# axiom_beta_sensor_cmv12000_tht_v0_16_r1_.net
KiCad netlist of a schematic drawn in EAGLE
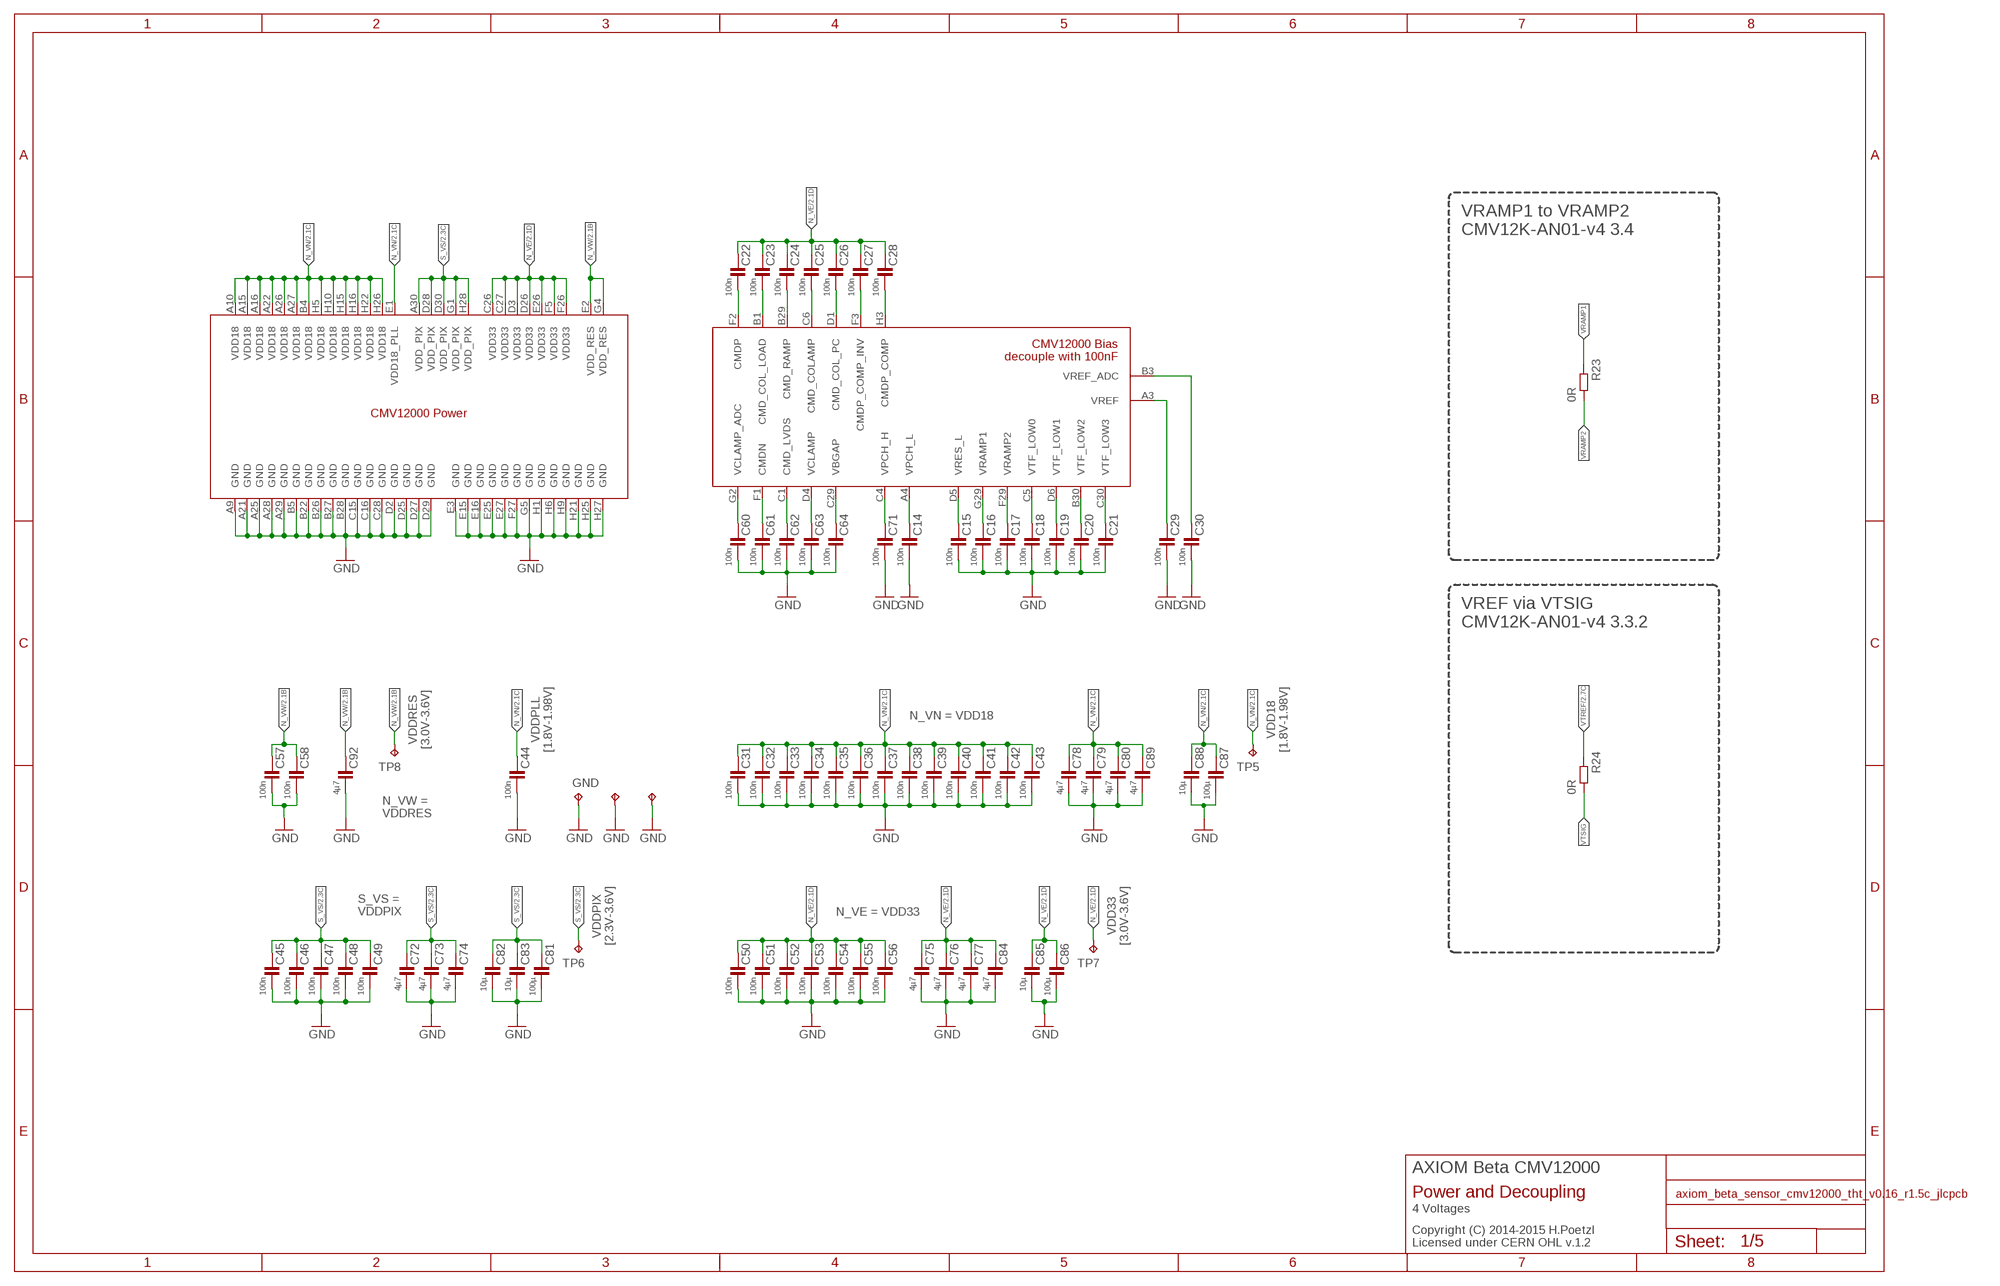
[diagram p0: schematic, sheet 1]
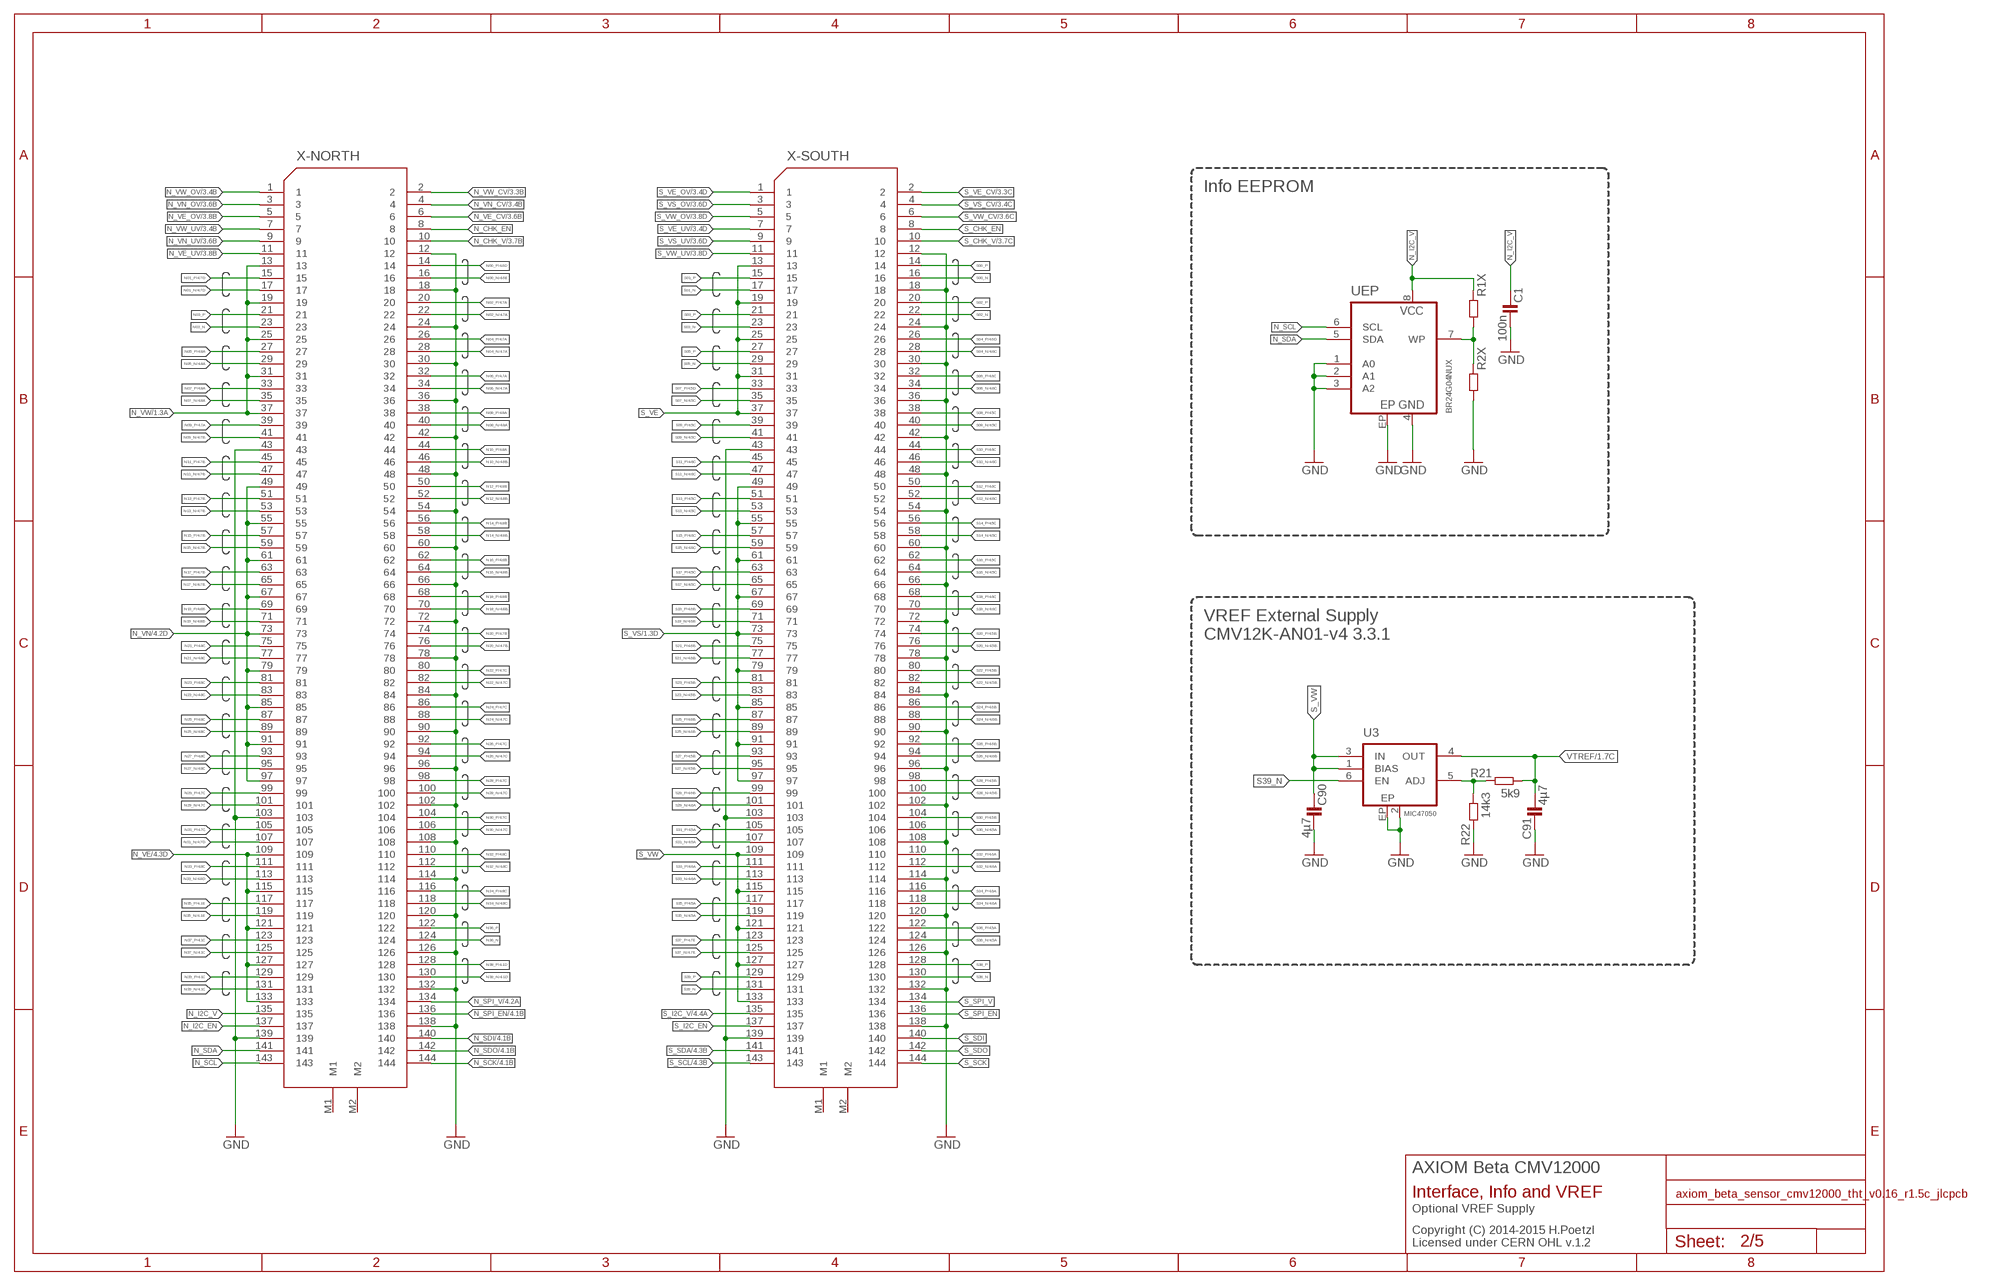
[diagram p1: schematic, sheet 2]
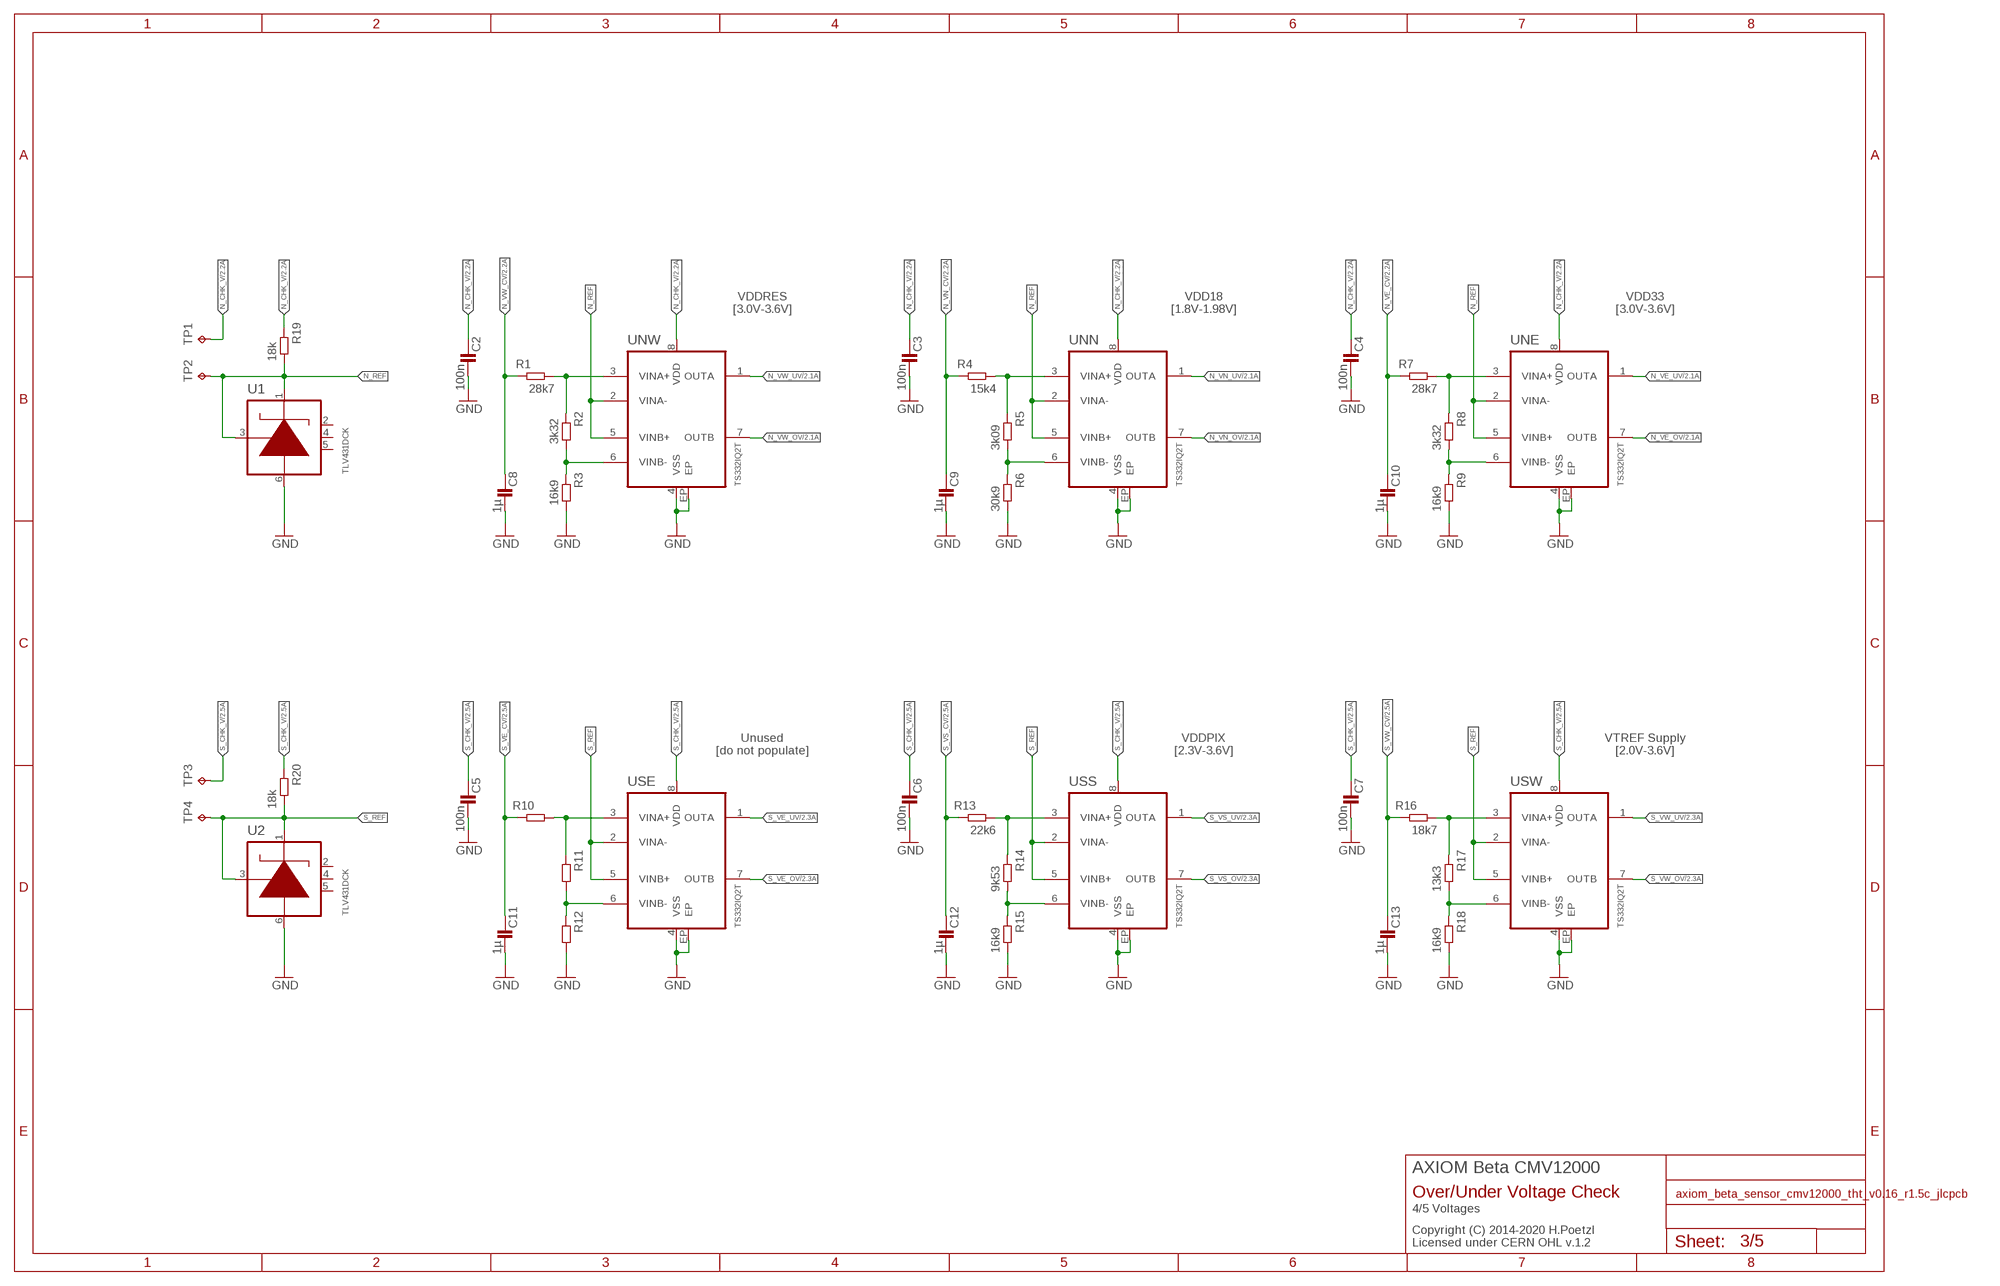
[diagram p2: schematic, sheet 3]
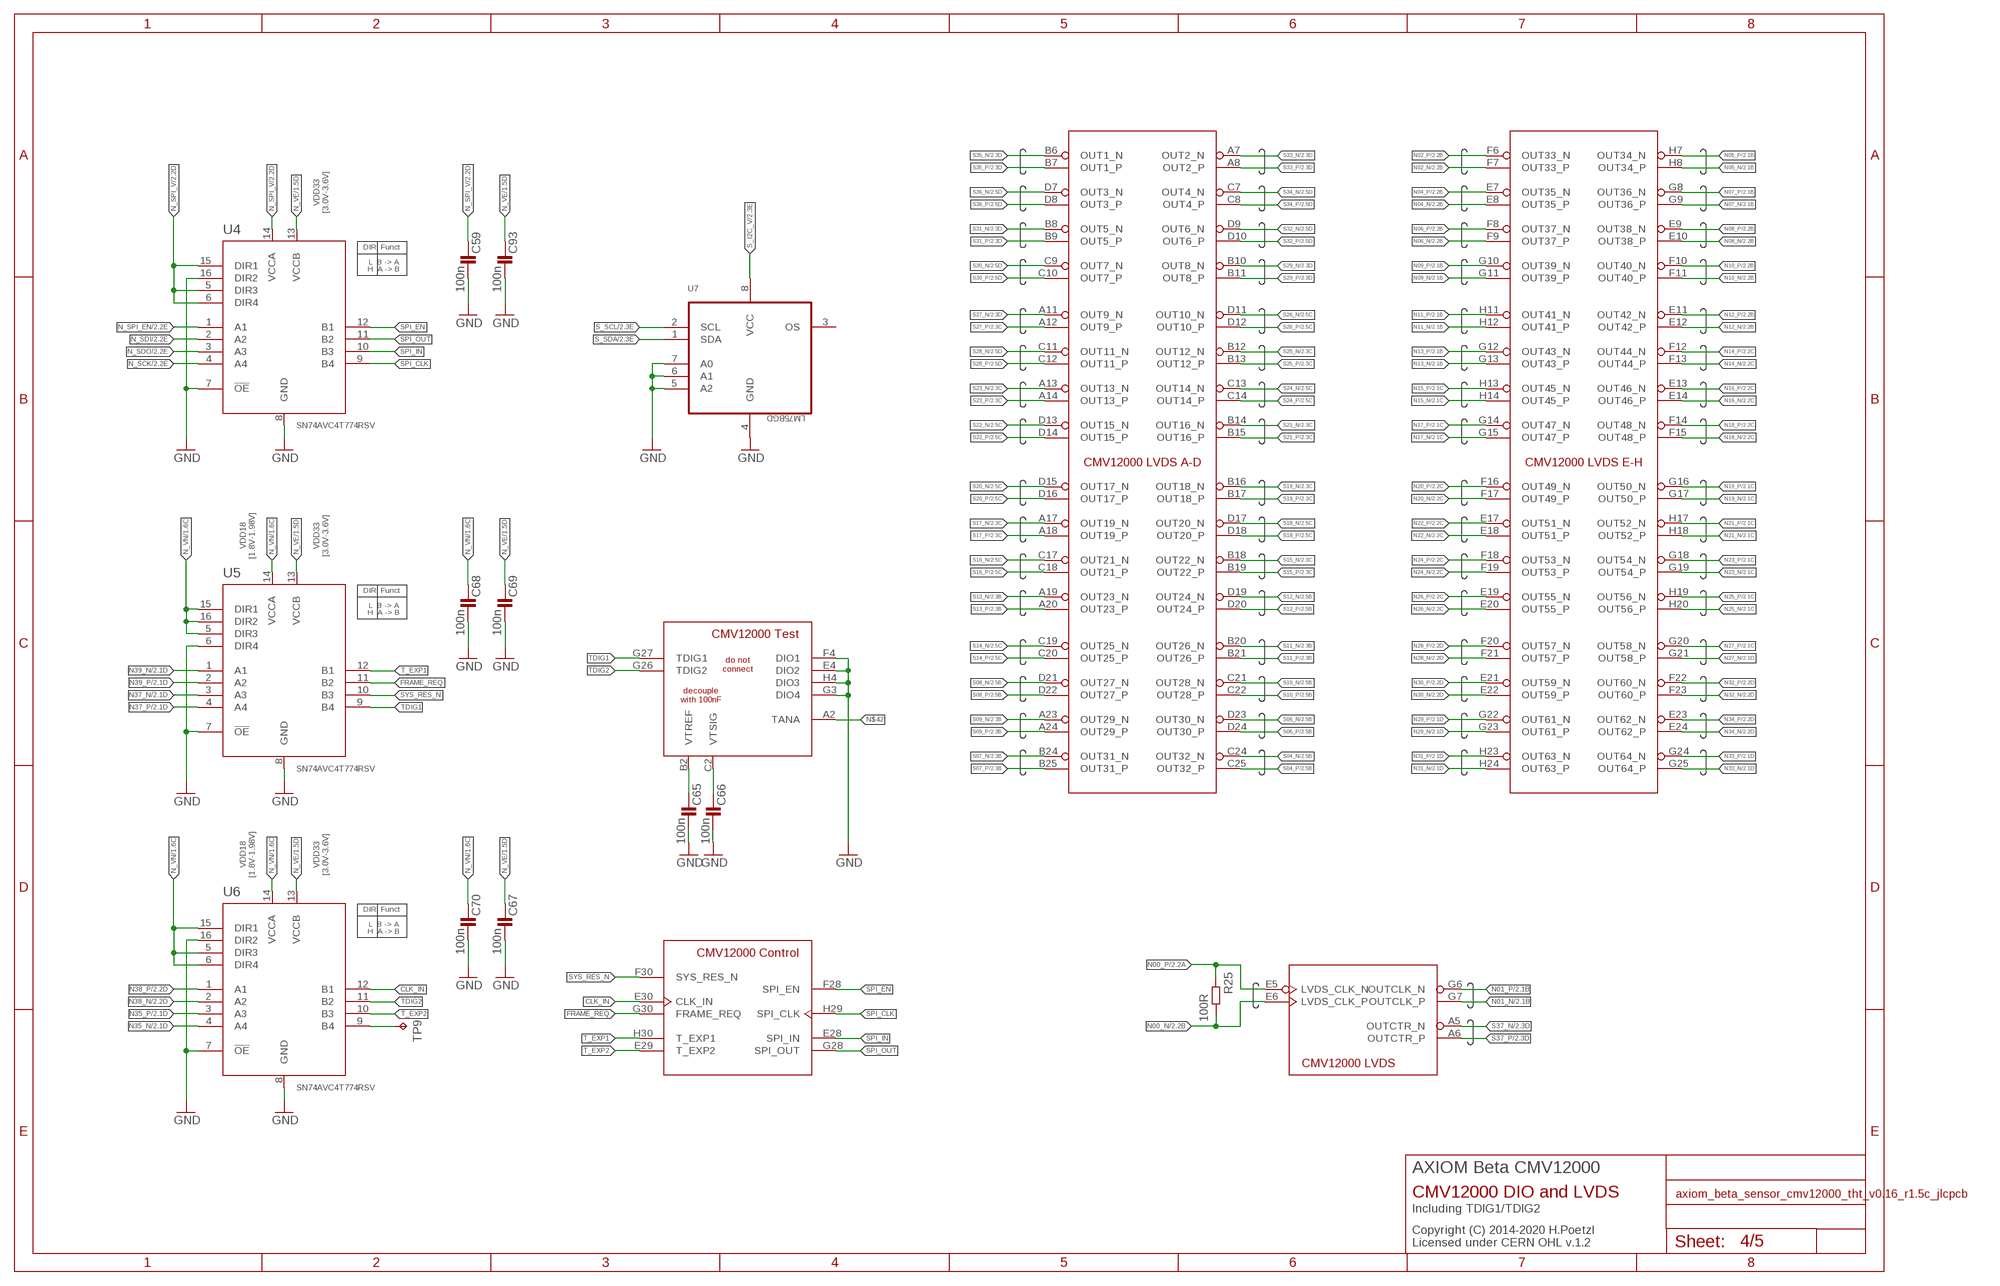
[diagram p3: schematic, sheet 4]
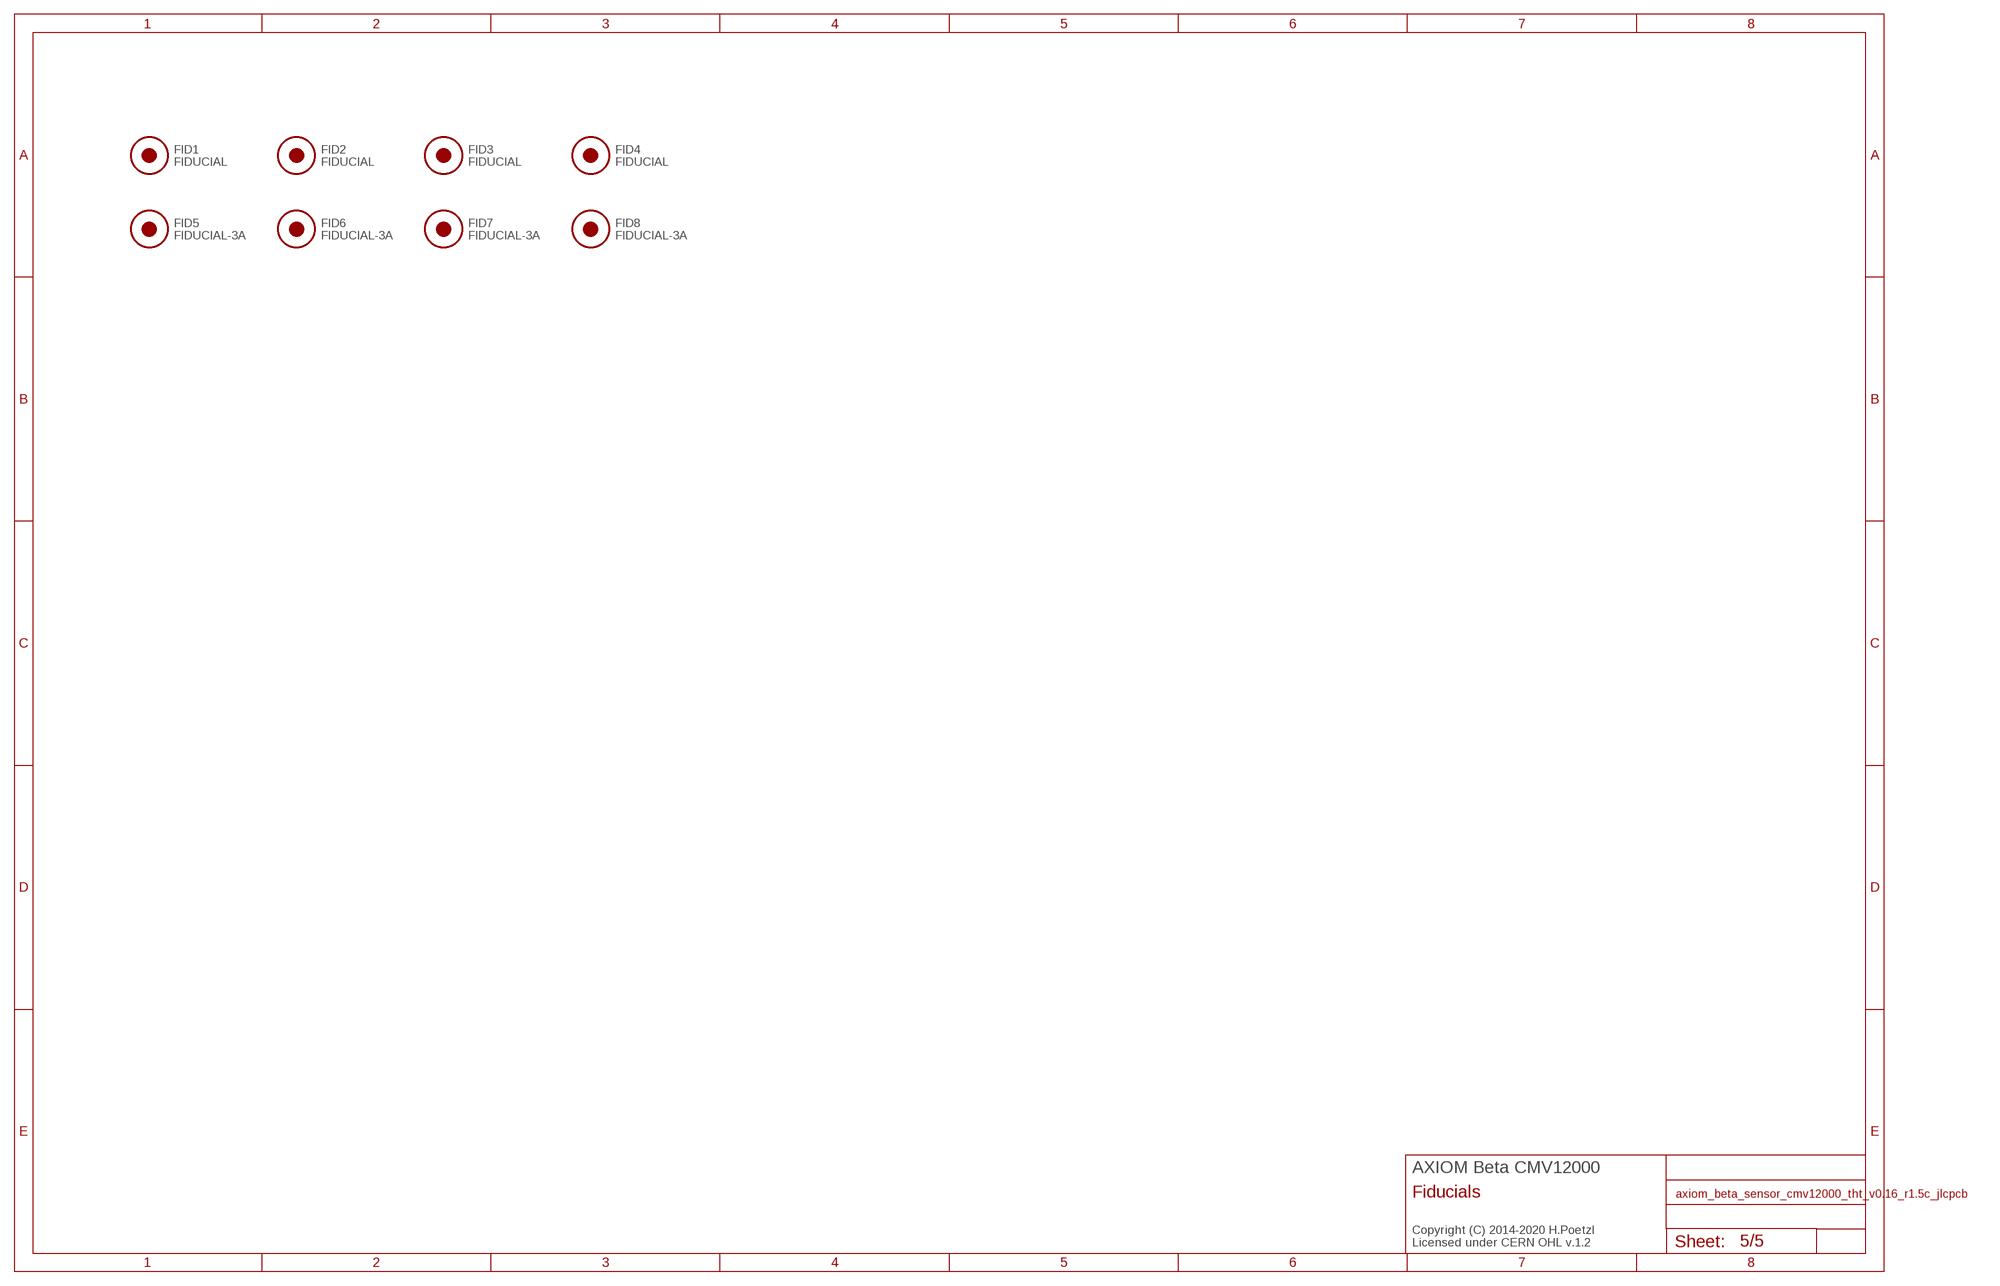
[diagram p4: schematic, sheet 5]

(export (version "E")
  (design (tool "Eeschema 10.0.6"))
  (components
    (comp (ref "C2")
      (value "100n")
      (footprint "eagle-import:0402-C")
      (libsource (lib "eagle-import") (part "C0402-C"))
    )
    (comp (ref "C3")
      (value "100n")
      (footprint "eagle-import:0402-C")
      (libsource (lib "eagle-import") (part "C0402-C"))
    )
    (comp (ref "C4")
      (value "100n")
      (footprint "eagle-import:0402-C")
      (libsource (lib "eagle-import") (part "C0402-C"))
    )
    (comp (ref "C5")
      (value "100n")
      (footprint "eagle-import:0402-C")
      (libsource (lib "eagle-import") (part "C0402-C"))
    )
    (comp (ref "C6")
      (value "100n")
      (footprint "eagle-import:0402-C")
      (libsource (lib "eagle-import") (part "C0402-C"))
    )
    (comp (ref "C7")
      (value "100n")
      (footprint "eagle-import:0402-C")
      (libsource (lib "eagle-import") (part "C0402-C"))
    )
    (comp (ref "C8")
      (value "1µ")
      (footprint "eagle-import:0402-C")
      (libsource (lib "eagle-import") (part "C0402-C"))
    )
    (comp (ref "C9")
      (value "1µ")
      (footprint "eagle-import:0402-C")
      (libsource (lib "eagle-import") (part "C0402-C"))
    )
    (comp (ref "C10")
      (value "1µ")
      (footprint "eagle-import:0402-C")
      (libsource (lib "eagle-import") (part "C0402-C"))
    )
    (comp (ref "C11")
      (value "1µ")
      (footprint "eagle-import:0402-C")
      (libsource (lib "eagle-import") (part "C0402-C"))
    )
    (comp (ref "C12")
      (value "1µ")
      (footprint "eagle-import:0402-C")
      (libsource (lib "eagle-import") (part "C0402-C"))
    )
    (comp (ref "C13")
      (value "1µ")
      (footprint "eagle-import:0402-C")
      (libsource (lib "eagle-import") (part "C0402-C"))
    )
    (comp (ref "R1")
      (value "28k7")
      (footprint "eagle-import:0402-C")
      (libsource (lib "eagle-import") (part "R0402-C"))
    )
    (comp (ref "R2")
      (value "3k32")
      (footprint "eagle-import:0402-C")
      (libsource (lib "eagle-import") (part "R0402-C"))
    )
    (comp (ref "R3")
      (value "16k9")
      (footprint "eagle-import:0402-C")
      (libsource (lib "eagle-import") (part "R0402-C"))
    )
    (comp (ref "R4")
      (value "15k4")
      (footprint "eagle-import:0402-C")
      (libsource (lib "eagle-import") (part "R0402-C"))
    )
    (comp (ref "R5")
      (value "3k09")
      (footprint "eagle-import:0402-C")
      (libsource (lib "eagle-import") (part "R0402-C"))
    )
    (comp (ref "R6")
      (value "30k9")
      (footprint "eagle-import:0402-C")
      (libsource (lib "eagle-import") (part "R0402-C"))
    )
    (comp (ref "R7")
      (value "28k7")
      (footprint "eagle-import:0402-C")
      (libsource (lib "eagle-import") (part "R0402-C"))
    )
    (comp (ref "R8")
      (value "3k32")
      (footprint "eagle-import:0402-C")
      (libsource (lib "eagle-import") (part "R0402-C"))
    )
    (comp (ref "R9")
      (value "16k9")
      (footprint "eagle-import:0402-C")
      (libsource (lib "eagle-import") (part "R0402-C"))
    )
    (comp (ref "R10")
      (value "R0402-C")
      (footprint "eagle-import:0402-C")
      (libsource (lib "eagle-import") (part "R0402-C"))
    )
    (comp (ref "R11")
      (value "R0402-C")
      (footprint "eagle-import:0402-C")
      (libsource (lib "eagle-import") (part "R0402-C"))
    )
    (comp (ref "R12")
      (value "R0402-C")
      (footprint "eagle-import:0402-C")
      (libsource (lib "eagle-import") (part "R0402-C"))
    )
    (comp (ref "R13")
      (value "22k6")
      (footprint "eagle-import:0402-C")
      (libsource (lib "eagle-import") (part "R0402-C"))
    )
    (comp (ref "R14")
      (value "9k53")
      (footprint "eagle-import:0402-C")
      (libsource (lib "eagle-import") (part "R0402-C"))
    )
    (comp (ref "R15")
      (value "16k9")
      (footprint "eagle-import:0402-C")
      (libsource (lib "eagle-import") (part "R0402-C"))
    )
    (comp (ref "R16")
      (value "18k7")
      (footprint "eagle-import:0402-C")
      (libsource (lib "eagle-import") (part "R0402-C"))
    )
    (comp (ref "R17")
      (value "13k3")
      (footprint "eagle-import:0402-C")
      (libsource (lib "eagle-import") (part "R0402-C"))
    )
    (comp (ref "R18")
      (value "16k9")
      (footprint "eagle-import:0402-C")
      (libsource (lib "eagle-import") (part "R0402-C"))
    )
    (comp (ref "R19")
      (value "18k")
      (footprint "eagle-import:0402-C")
      (libsource (lib "eagle-import") (part "R0402-C"))
    )
    (comp (ref "R20")
      (value "18k")
      (footprint "eagle-import:0402-C")
      (libsource (lib "eagle-import") (part "R0402-C"))
    )
    (comp (ref "TP1")
      (value "TPTP10R")
      (footprint "eagle-import:TP10R")
      (libsource (lib "eagle-import") (part "TPTP10R"))
    )
    (comp (ref "TP2")
      (value "TPTP10R")
      (footprint "eagle-import:TP10R")
      (libsource (lib "eagle-import") (part "TPTP10R"))
    )
    (comp (ref "TP3")
      (value "TPTP10R")
      (footprint "eagle-import:TP10R")
      (libsource (lib "eagle-import") (part "TPTP10R"))
    )
    (comp (ref "TP4")
      (value "TPTP10R")
      (footprint "eagle-import:TP10R")
      (libsource (lib "eagle-import") (part "TPTP10R"))
    )
    (comp (ref "U1")
      (value "TLV431DCK")
      (footprint "eagle-import:SOT65P210X110-6N")
      (libsource (lib "eagle-import") (part "TLV431DCK"))
    )
    (comp (ref "U2")
      (value "TLV431DCK")
      (footprint "eagle-import:SOT65P210X110-6N")
      (libsource (lib "eagle-import") (part "TLV431DCK"))
    )
    (comp (ref "UNE")
      (value "TS332IQ2T")
      (footprint "eagle-import:DFN200X200X100-9N")
      (libsource (lib "eagle-import") (part "TS332IQ2T"))
    )
    (comp (ref "UNN")
      (value "TS332IQ2T")
      (footprint "eagle-import:DFN200X200X100-9N")
      (libsource (lib "eagle-import") (part "TS332IQ2T"))
    )
    (comp (ref "UNW")
      (value "TS332IQ2T")
      (footprint "eagle-import:DFN200X200X100-9N")
      (libsource (lib "eagle-import") (part "TS332IQ2T"))
    )
    (comp (ref "USE")
      (value "TS332IQ2T")
      (footprint "eagle-import:DFN200X200X100-9N")
      (libsource (lib "eagle-import") (part "TS332IQ2T"))
    )
    (comp (ref "USS")
      (value "TS332IQ2T")
      (footprint "eagle-import:DFN200X200X100-9N")
      (libsource (lib "eagle-import") (part "TS332IQ2T"))
    )
    (comp (ref "USW")
      (value "TS332IQ2T")
      (footprint "eagle-import:DFN200X200X100-9N")
      (libsource (lib "eagle-import") (part "TS332IQ2T"))
    )
    (comp (ref "C14")
      (value "100n")
      (footprint "eagle-import:0402-C")
      (libsource (lib "eagle-import") (part "C0402-C"))
    )
    (comp (ref "C15")
      (value "100n")
      (footprint "eagle-import:0402-C")
      (libsource (lib "eagle-import") (part "C0402-C"))
    )
    (comp (ref "C16")
      (value "100n")
      (footprint "eagle-import:0402-C")
      (libsource (lib "eagle-import") (part "C0402-C"))
    )
    (comp (ref "C17")
      (value "100n")
      (footprint "eagle-import:0402-C")
      (libsource (lib "eagle-import") (part "C0402-C"))
    )
    (comp (ref "C18")
      (value "100n")
      (footprint "eagle-import:0402-C")
      (libsource (lib "eagle-import") (part "C0402-C"))
    )
    (comp (ref "C19")
      (value "100n")
      (footprint "eagle-import:0402-C")
      (libsource (lib "eagle-import") (part "C0402-C"))
    )
    (comp (ref "C20")
      (value "100n")
      (footprint "eagle-import:0402-C")
      (libsource (lib "eagle-import") (part "C0402-C"))
    )
    (comp (ref "C21")
      (value "100n")
      (footprint "eagle-import:0402-C")
      (libsource (lib "eagle-import") (part "C0402-C"))
    )
    (comp (ref "C22")
      (value "100n")
      (footprint "eagle-import:0402-C")
      (libsource (lib "eagle-import") (part "C0402-C"))
    )
    (comp (ref "C23")
      (value "100n")
      (footprint "eagle-import:0402-C")
      (libsource (lib "eagle-import") (part "C0402-C"))
    )
    (comp (ref "C24")
      (value "100n")
      (footprint "eagle-import:0402-C")
      (libsource (lib "eagle-import") (part "C0402-C"))
    )
    (comp (ref "C25")
      (value "100n")
      (footprint "eagle-import:0402-C")
      (libsource (lib "eagle-import") (part "C0402-C"))
    )
    (comp (ref "C26")
      (value "100n")
      (footprint "eagle-import:0402-C")
      (libsource (lib "eagle-import") (part "C0402-C"))
    )
    (comp (ref "C27")
      (value "100n")
      (footprint "eagle-import:0402-C")
      (libsource (lib "eagle-import") (part "C0402-C"))
    )
    (comp (ref "C28")
      (value "100n")
      (footprint "eagle-import:0402-C")
      (libsource (lib "eagle-import") (part "C0402-C"))
    )
    (comp (ref "C29")
      (value "100n")
      (footprint "eagle-import:0402-C")
      (libsource (lib "eagle-import") (part "C0402-C"))
    )
    (comp (ref "C30")
      (value "100n")
      (footprint "eagle-import:0402-C")
      (libsource (lib "eagle-import") (part "C0402-C"))
    )
    (comp (ref "C31")
      (value "100n")
      (footprint "eagle-import:0402-C")
      (libsource (lib "eagle-import") (part "C0402-C"))
    )
    (comp (ref "C32")
      (value "100n")
      (footprint "eagle-import:0402-C")
      (libsource (lib "eagle-import") (part "C0402-C"))
    )
    (comp (ref "C33")
      (value "100n")
      (footprint "eagle-import:0402-C")
      (libsource (lib "eagle-import") (part "C0402-C"))
    )
    (comp (ref "C34")
      (value "100n")
      (footprint "eagle-import:0402-C")
      (libsource (lib "eagle-import") (part "C0402-C"))
    )
    (comp (ref "C35")
      (value "100n")
      (footprint "eagle-import:0402-C")
      (libsource (lib "eagle-import") (part "C0402-C"))
    )
    (comp (ref "C36")
      (value "100n")
      (footprint "eagle-import:0402-C")
      (libsource (lib "eagle-import") (part "C0402-C"))
    )
    (comp (ref "C37")
      (value "100n")
      (footprint "eagle-import:0402-C")
      (libsource (lib "eagle-import") (part "C0402-C"))
    )
    (comp (ref "C38")
      (value "100n")
      (footprint "eagle-import:0402-C")
      (libsource (lib "eagle-import") (part "C0402-C"))
    )
    (comp (ref "C39")
      (value "100n")
      (footprint "eagle-import:0402-C")
      (libsource (lib "eagle-import") (part "C0402-C"))
    )
    (comp (ref "C40")
      (value "100n")
      (footprint "eagle-import:0402-C")
      (libsource (lib "eagle-import") (part "C0402-C"))
    )
    (comp (ref "C41")
      (value "100n")
      (footprint "eagle-import:0402-C")
      (libsource (lib "eagle-import") (part "C0402-C"))
    )
    (comp (ref "C42")
      (value "100n")
      (footprint "eagle-import:0402-C")
      (libsource (lib "eagle-import") (part "C0402-C"))
    )
    (comp (ref "C43")
      (value "100n")
      (footprint "eagle-import:0402-C")
      (libsource (lib "eagle-import") (part "C0402-C"))
    )
    (comp (ref "C44")
      (value "100n")
      (footprint "eagle-import:0402-C")
      (libsource (lib "eagle-import") (part "C0402-C"))
    )
    (comp (ref "C45")
      (value "100n")
      (footprint "eagle-import:0402-C")
      (libsource (lib "eagle-import") (part "C0402-C"))
    )
    (comp (ref "C46")
      (value "100n")
      (footprint "eagle-import:0402-C")
      (libsource (lib "eagle-import") (part "C0402-C"))
    )
    (comp (ref "C47")
      (value "100n")
      (footprint "eagle-import:0402-C")
      (libsource (lib "eagle-import") (part "C0402-C"))
    )
    (comp (ref "C48")
      (value "100n")
      (footprint "eagle-import:0402-C")
      (libsource (lib "eagle-import") (part "C0402-C"))
    )
    (comp (ref "C49")
      (value "100n")
      (footprint "eagle-import:0402-C")
      (libsource (lib "eagle-import") (part "C0402-C"))
    )
    (comp (ref "C50")
      (value "100n")
      (footprint "eagle-import:0402-C")
      (libsource (lib "eagle-import") (part "C0402-C"))
    )
    (comp (ref "C51")
      (value "100n")
      (footprint "eagle-import:0402-C")
      (libsource (lib "eagle-import") (part "C0402-C"))
    )
    (comp (ref "C52")
      (value "100n")
      (footprint "eagle-import:0402-C")
      (libsource (lib "eagle-import") (part "C0402-C"))
    )
    (comp (ref "C53")
      (value "100n")
      (footprint "eagle-import:0402-C")
      (libsource (lib "eagle-import") (part "C0402-C"))
    )
    (comp (ref "C54")
      (value "100n")
      (footprint "eagle-import:0402-C")
      (libsource (lib "eagle-import") (part "C0402-C"))
    )
    (comp (ref "C55")
      (value "100n")
      (footprint "eagle-import:0402-C")
      (libsource (lib "eagle-import") (part "C0402-C"))
    )
    (comp (ref "C56")
      (value "100n")
      (footprint "eagle-import:0402-C")
      (libsource (lib "eagle-import") (part "C0402-C"))
    )
    (comp (ref "C57")
      (value "100n")
      (footprint "eagle-import:0402-C")
      (libsource (lib "eagle-import") (part "C0402-C"))
    )
    (comp (ref "C58")
      (value "100n")
      (footprint "eagle-import:0402-C")
      (libsource (lib "eagle-import") (part "C0402-C"))
    )
    (comp (ref "C60")
      (value "100n")
      (footprint "eagle-import:0402-C")
      (libsource (lib "eagle-import") (part "C0402-C"))
    )
    (comp (ref "C61")
      (value "100n")
      (footprint "eagle-import:0402-C")
      (libsource (lib "eagle-import") (part "C0402-C"))
    )
    (comp (ref "C62")
      (value "100n")
      (footprint "eagle-import:0402-C")
      (libsource (lib "eagle-import") (part "C0402-C"))
    )
    (comp (ref "C63")
      (value "100n")
      (footprint "eagle-import:0402-C")
      (libsource (lib "eagle-import") (part "C0402-C"))
    )
    (comp (ref "C64")
      (value "100n")
      (footprint "eagle-import:0402-C")
      (libsource (lib "eagle-import") (part "C0402-C"))
    )
    (comp (ref "C71")
      (value "100n")
      (footprint "eagle-import:0402-C")
      (libsource (lib "eagle-import") (part "C0402-C"))
    )
    (comp (ref "C72")
      (value "4µ7")
      (footprint "eagle-import:0402-B")
      (libsource (lib "eagle-import") (part "C0402-B"))
    )
    (comp (ref "C73")
      (value "4µ7")
      (footprint "eagle-import:0402-C")
      (libsource (lib "eagle-import") (part "C0402-C"))
    )
    (comp (ref "C74")
      (value "4µ7")
      (footprint "eagle-import:0402-C")
      (libsource (lib "eagle-import") (part "C0402-C"))
    )
    (comp (ref "C75")
      (value "4µ7")
      (footprint "eagle-import:0402-C")
      (libsource (lib "eagle-import") (part "C0402-C"))
    )
    (comp (ref "C76")
      (value "4µ7")
      (footprint "eagle-import:0402-C")
      (libsource (lib "eagle-import") (part "C0402-C"))
    )
    (comp (ref "C77")
      (value "4µ7")
      (footprint "eagle-import:0402-B")
      (libsource (lib "eagle-import") (part "C0402-B"))
    )
    (comp (ref "C78")
      (value "4µ7")
      (footprint "eagle-import:0402-B")
      (libsource (lib "eagle-import") (part "C0402-B"))
    )
    (comp (ref "C79")
      (value "4µ7")
      (footprint "eagle-import:0402-C")
      (libsource (lib "eagle-import") (part "C0402-C"))
    )
    (comp (ref "C80")
      (value "4µ7")
      (footprint "eagle-import:0402-C")
      (libsource (lib "eagle-import") (part "C0402-C"))
    )
    (comp (ref "C81")
      (value "100µ")
      (footprint "eagle-import:1206-B")
      (libsource (lib "eagle-import") (part "C1206-B"))
    )
    (comp (ref "C82")
      (value "10µ")
      (footprint "eagle-import:0603-C")
      (libsource (lib "eagle-import") (part "C0603-C"))
    )
    (comp (ref "C83")
      (value "10µ")
      (footprint "eagle-import:0603-C")
      (libsource (lib "eagle-import") (part "C0603-C"))
    )
    (comp (ref "C84")
      (value "4µ7")
      (footprint "eagle-import:0402-C")
      (libsource (lib "eagle-import") (part "C0402-C"))
    )
    (comp (ref "C85")
      (value "10µ")
      (footprint "eagle-import:0603-C")
      (libsource (lib "eagle-import") (part "C0603-C"))
    )
    (comp (ref "C86")
      (value "100µ")
      (footprint "eagle-import:1206-B")
      (libsource (lib "eagle-import") (part "C1206-B"))
    )
    (comp (ref "C87")
      (value "100µ")
      (footprint "eagle-import:1206-B")
      (libsource (lib "eagle-import") (part "C1206-B"))
    )
    (comp (ref "C88")
      (value "10µ")
      (footprint "eagle-import:0603-C")
      (libsource (lib "eagle-import") (part "C0603-C"))
    )
    (comp (ref "C89")
      (value "4µ7")
      (footprint "eagle-import:0402-C")
      (libsource (lib "eagle-import") (part "C0402-C"))
    )
    (comp (ref "C92")
      (value "4µ7")
      (footprint "eagle-import:0402-C")
      (libsource (lib "eagle-import") (part "C0402-C"))
    )
    (comp (ref "GND")
      (value "TPTP10R")
      (footprint "eagle-import:TP10R")
      (libsource (lib "eagle-import") (part "TPTP10R"))
    )
    (comp (ref "GND75")
      (value "TPTP10R")
      (footprint "eagle-import:TP10R")
      (libsource (lib "eagle-import") (part "TPTP10R"))
    )
    (comp (ref "GND77")
      (value "TPTP10R")
      (footprint "eagle-import:TP10R")
      (libsource (lib "eagle-import") (part "TPTP10R"))
    )
    (comp (ref "R23")
      (value "0R")
      (footprint "eagle-import:0402-C")
      (libsource (lib "eagle-import") (part "R0402-C"))
    )
    (comp (ref "R24")
      (value "0R")
      (footprint "eagle-import:0402-C")
      (libsource (lib "eagle-import") (part "R0402-C"))
    )
    (comp (ref "SENSOR")
      (value "CMV12000JLCPCB")
      (footprint "eagle-import:10-30-07-237-400T4-JLCPCB")
      (libsource (lib "eagle-import") (part "CMV12000JLCPCB"))
    )
    (comp (ref "TP5")
      (value "TPTP10R")
      (footprint "eagle-import:TP10R")
      (libsource (lib "eagle-import") (part "TPTP10R"))
    )
    (comp (ref "TP6")
      (value "TPTP10R")
      (footprint "eagle-import:TP10R")
      (libsource (lib "eagle-import") (part "TPTP10R"))
    )
    (comp (ref "TP7")
      (value "TPTP10R")
      (footprint "eagle-import:TP10R")
      (libsource (lib "eagle-import") (part "TPTP10R"))
    )
    (comp (ref "TP8")
      (value "TPTP10R")
      (footprint "eagle-import:TP10R")
      (libsource (lib "eagle-import") (part "TPTP10R"))
    )
    (comp (ref "FID1")
      (value "FIDUCIAL")
      (footprint "eagle-import:FID_ARROW")
      (libsource (lib "eagle-import") (part "FIDUCIAL"))
    )
    (comp (ref "FID2")
      (value "FIDUCIAL")
      (footprint "eagle-import:FID_ARROW")
      (libsource (lib "eagle-import") (part "FIDUCIAL"))
    )
    (comp (ref "FID3")
      (value "FIDUCIAL")
      (footprint "eagle-import:FID_ARROW")
      (libsource (lib "eagle-import") (part "FIDUCIAL"))
    )
    (comp (ref "FID4")
      (value "FIDUCIAL")
      (footprint "eagle-import:FID_ARROW")
      (libsource (lib "eagle-import") (part "FIDUCIAL"))
    )
    (comp (ref "FID5")
      (value "FIDUCIAL-3A")
      (footprint "eagle-import:FID_3ARROW")
      (libsource (lib "eagle-import") (part "FIDUCIAL-3A"))
    )
    (comp (ref "FID6")
      (value "FIDUCIAL-3A")
      (footprint "eagle-import:FID_3ARROW")
      (libsource (lib "eagle-import") (part "FIDUCIAL-3A"))
    )
    (comp (ref "FID7")
      (value "FIDUCIAL-3A")
      (footprint "eagle-import:FID_3ARROW")
      (libsource (lib "eagle-import") (part "FIDUCIAL-3A"))
    )
    (comp (ref "FID8")
      (value "FIDUCIAL-3A")
      (footprint "eagle-import:FID_3ARROW")
      (libsource (lib "eagle-import") (part "FIDUCIAL-3A"))
    )
    (comp (ref "C1")
      (value "100n")
      (footprint "eagle-import:0402-C")
      (libsource (lib "eagle-import") (part "C0402-C"))
    )
    (comp (ref "C90")
      (value "4µ7")
      (footprint "eagle-import:0402-C")
      (libsource (lib "eagle-import") (part "C0402-C"))
    )
    (comp (ref "C91")
      (value "4µ7")
      (footprint "eagle-import:0402-C")
      (libsource (lib "eagle-import") (part "C0402-C"))
    )
    (comp (ref "R1X")
      (value "R0402-C")
      (footprint "eagle-import:0402-C")
      (libsource (lib "eagle-import") (part "R0402-C"))
    )
    (comp (ref "R2X")
      (value "R0402-C")
      (footprint "eagle-import:0402-C")
      (libsource (lib "eagle-import") (part "R0402-C"))
    )
    (comp (ref "R21")
      (value "5k9")
      (footprint "eagle-import:0402-C")
      (libsource (lib "eagle-import") (part "R0402-C"))
    )
    (comp (ref "R22")
      (value "14k3")
      (footprint "eagle-import:0402-C")
      (libsource (lib "eagle-import") (part "R0402-C"))
    )
    (comp (ref "U3")
      (value "MIC47050")
      (footprint "eagle-import:MLF-6")
      (libsource (lib "eagle-import") (part "MIC47050-ADJ"))
    )
    (comp (ref "UEP")
      (value "BR24G04NUX")
      (footprint "eagle-import:DFN200X300X100-9N")
      (libsource (lib "eagle-import") (part "BR24G04NUX"))
    )
    (comp (ref "X-NORTH")
      (value "FX10-144P")
      (footprint "eagle-import:FX10A-144P")
      (libsource (lib "eagle-import") (part "FX10-144P"))
    )
    (comp (ref "X-SOUTH")
      (value "FX10-144P")
      (footprint "eagle-import:FX10A-144P")
      (libsource (lib "eagle-import") (part "FX10-144P"))
    )
    (comp (ref "C59")
      (value "100n")
      (footprint "eagle-import:0402-C")
      (libsource (lib "eagle-import") (part "C0402-C"))
    )
    (comp (ref "C65")
      (value "100n")
      (footprint "eagle-import:0402-C")
      (libsource (lib "eagle-import") (part "C0402-C"))
    )
    (comp (ref "C66")
      (value "100n")
      (footprint "eagle-import:0402-C")
      (libsource (lib "eagle-import") (part "C0402-C"))
    )
    (comp (ref "C67")
      (value "100n")
      (footprint "eagle-import:0402-C")
      (libsource (lib "eagle-import") (part "C0402-C"))
    )
    (comp (ref "C68")
      (value "100n")
      (footprint "eagle-import:0402-C")
      (libsource (lib "eagle-import") (part "C0402-C"))
    )
    (comp (ref "C69")
      (value "100n")
      (footprint "eagle-import:0402-C")
      (libsource (lib "eagle-import") (part "C0402-C"))
    )
    (comp (ref "C70")
      (value "100n")
      (footprint "eagle-import:0402-C")
      (libsource (lib "eagle-import") (part "C0402-C"))
    )
    (comp (ref "C93")
      (value "100n")
      (footprint "eagle-import:0402-C")
      (libsource (lib "eagle-import") (part "C0402-C"))
    )
    (comp (ref "R25")
      (value "100R")
      (footprint "eagle-import:0402-C")
      (libsource (lib "eagle-import") (part "R0402-C"))
    )
    (comp (ref "TP9")
      (value "TPTP10R")
      (footprint "eagle-import:TP10R")
      (libsource (lib "eagle-import") (part "TPTP10R"))
    )
    (comp (ref "U4")
      (value "SN74AVC4T774RSV")
      (footprint "eagle-import:QFN40P185X265X55-16N")
      (libsource (lib "eagle-import") (part "SN74AVC4T774RSV"))
    )
    (comp (ref "U5")
      (value "SN74AVC4T774RSV")
      (footprint "eagle-import:QFN40P185X265X55-16N")
      (libsource (lib "eagle-import") (part "SN74AVC4T774RSV"))
    )
    (comp (ref "U6")
      (value "SN74AVC4T774RSV")
      (footprint "eagle-import:QFN40P185X265X55-16N")
      (libsource (lib "eagle-import") (part "SN74AVC4T774RSV"))
    )
    (comp (ref "U7")
      (value "LM75BGD")
      (footprint "eagle-import:SOT996-2_3")
      (libsource (lib "eagle-import") (part "LM75BGD"))
    )
  )
  (nets
    (net (code "1") (name "CLK_IN") (class "Default")
      (node (ref "SENSOR") (pin "E30") (pinfunction "CLK_IN_E30") (pintype "input"))
      (node (ref "U6") (pin "12") (pinfunction "B1_12") (pintype "bidirectional"))
    )
    (net (code "2") (name "FRAME_REQ") (class "Default")
      (node (ref "SENSOR") (pin "G30") (pinfunction "FRAME_REQ_G30") (pintype "input"))
      (node (ref "U5") (pin "11") (pinfunction "B2_11") (pintype "bidirectional"))
    )
    (net (code "3") (name "GND") (class "Default")
      (node (ref "C1") (pin "2") (pinfunction "2_2") (pintype "passive"))
      (node (ref "C10") (pin "2") (pinfunction "2_2") (pintype "passive"))
      (node (ref "C11") (pin "2") (pinfunction "2_2") (pintype "passive"))
      (node (ref "C12") (pin "2") (pinfunction "2_2") (pintype "passive"))
      (node (ref "C13") (pin "2") (pinfunction "2_2") (pintype "passive"))
      (node (ref "C14") (pin "2") (pinfunction "2_2") (pintype "passive"))
      (node (ref "C15") (pin "2") (pinfunction "2_2") (pintype "passive"))
      (node (ref "C16") (pin "2") (pinfunction "2_2") (pintype "passive"))
      (node (ref "C17") (pin "2") (pinfunction "2_2") (pintype "passive"))
      (node (ref "C18") (pin "2") (pinfunction "2_2") (pintype "passive"))
      (node (ref "C19") (pin "2") (pinfunction "2_2") (pintype "passive"))
      (node (ref "C2") (pin "2") (pinfunction "2_2") (pintype "passive"))
      (node (ref "C20") (pin "2") (pinfunction "2_2") (pintype "passive"))
      (node (ref "C21") (pin "2") (pinfunction "2_2") (pintype "passive"))
      (node (ref "C29") (pin "2") (pinfunction "2_2") (pintype "passive"))
      (node (ref "C3") (pin "2") (pinfunction "2_2") (pintype "passive"))
      (node (ref "C30") (pin "2") (pinfunction "2_2") (pintype "passive"))
      (node (ref "C31") (pin "2") (pinfunction "2_2") (pintype "passive"))
      (node (ref "C32") (pin "2") (pinfunction "2_2") (pintype "passive"))
      (node (ref "C33") (pin "2") (pinfunction "2_2") (pintype "passive"))
      (node (ref "C34") (pin "2") (pinfunction "2_2") (pintype "passive"))
      (node (ref "C35") (pin "2") (pinfunction "2_2") (pintype "passive"))
      (node (ref "C36") (pin "2") (pinfunction "2_2") (pintype "passive"))
      (node (ref "C37") (pin "2") (pinfunction "2_2") (pintype "passive"))
      (node (ref "C38") (pin "2") (pinfunction "2_2") (pintype "passive"))
      (node (ref "C39") (pin "2") (pinfunction "2_2") (pintype "passive"))
      (node (ref "C4") (pin "2") (pinfunction "2_2") (pintype "passive"))
      (node (ref "C40") (pin "2") (pinfunction "2_2") (pintype "passive"))
      (node (ref "C41") (pin "2") (pinfunction "2_2") (pintype "passive"))
      (node (ref "C42") (pin "2") (pinfunction "2_2") (pintype "passive"))
      (node (ref "C43") (pin "2") (pinfunction "2_2") (pintype "passive"))
      (node (ref "C44") (pin "2") (pinfunction "2_2") (pintype "passive"))
      (node (ref "C45") (pin "2") (pinfunction "2_2") (pintype "passive"))
      (node (ref "C46") (pin "2") (pinfunction "2_2") (pintype "passive"))
      (node (ref "C47") (pin "2") (pinfunction "2_2") (pintype "passive"))
      (node (ref "C48") (pin "2") (pinfunction "2_2") (pintype "passive"))
      (node (ref "C49") (pin "2") (pinfunction "2_2") (pintype "passive"))
      (node (ref "C5") (pin "2") (pinfunction "2_2") (pintype "passive"))
      (node (ref "C50") (pin "2") (pinfunction "2_2") (pintype "passive"))
      (node (ref "C51") (pin "2") (pinfunction "2_2") (pintype "passive"))
      (node (ref "C52") (pin "2") (pinfunction "2_2") (pintype "passive"))
      (node (ref "C53") (pin "2") (pinfunction "2_2") (pintype "passive"))
      (node (ref "C54") (pin "2") (pinfunction "2_2") (pintype "passive"))
      (node (ref "C55") (pin "2") (pinfunction "2_2") (pintype "passive"))
      (node (ref "C56") (pin "2") (pinfunction "2_2") (pintype "passive"))
      (node (ref "C57") (pin "2") (pinfunction "2_2") (pintype "passive"))
      (node (ref "C58") (pin "2") (pinfunction "2_2") (pintype "passive"))
      (node (ref "C59") (pin "2") (pinfunction "2_2") (pintype "passive"))
      (node (ref "C6") (pin "2") (pinfunction "2_2") (pintype "passive"))
      (node (ref "C60") (pin "2") (pinfunction "2_2") (pintype "passive"))
      (node (ref "C61") (pin "2") (pinfunction "2_2") (pintype "passive"))
      (node (ref "C62") (pin "2") (pinfunction "2_2") (pintype "passive"))
      (node (ref "C63") (pin "2") (pinfunction "2_2") (pintype "passive"))
      (node (ref "C64") (pin "2") (pinfunction "2_2") (pintype "passive"))
      (node (ref "C65") (pin "2") (pinfunction "2_2") (pintype "passive"))
      (node (ref "C66") (pin "2") (pinfunction "2_2") (pintype "passive"))
      (node (ref "C67") (pin "2") (pinfunction "2_2") (pintype "passive"))
      (node (ref "C68") (pin "2") (pinfunction "2_2") (pintype "passive"))
      (node (ref "C69") (pin "2") (pinfunction "2_2") (pintype "passive"))
      (node (ref "C7") (pin "2") (pinfunction "2_2") (pintype "passive"))
      (node (ref "C70") (pin "2") (pinfunction "2_2") (pintype "passive"))
      (node (ref "C71") (pin "2") (pinfunction "2_2") (pintype "passive"))
      (node (ref "C72") (pin "2") (pinfunction "2_2") (pintype "passive"))
      (node (ref "C73") (pin "2") (pinfunction "2_2") (pintype "passive"))
      (node (ref "C74") (pin "2") (pinfunction "2_2") (pintype "passive"))
      (node (ref "C75") (pin "2") (pinfunction "2_2") (pintype "passive"))
      (node (ref "C76") (pin "2") (pinfunction "2_2") (pintype "passive"))
      (node (ref "C77") (pin "2") (pinfunction "2_2") (pintype "passive"))
      (node (ref "C78") (pin "2") (pinfunction "2_2") (pintype "passive"))
      (node (ref "C79") (pin "2") (pinfunction "2_2") (pintype "passive"))
      (node (ref "C8") (pin "2") (pinfunction "2_2") (pintype "passive"))
      (node (ref "C80") (pin "2") (pinfunction "2_2") (pintype "passive"))
      (node (ref "C81") (pin "2") (pinfunction "2_2") (pintype "passive"))
      (node (ref "C82") (pin "2") (pinfunction "2_2") (pintype "passive"))
      (node (ref "C83") (pin "2") (pinfunction "2_2") (pintype "passive"))
      (node (ref "C84") (pin "2") (pinfunction "2_2") (pintype "passive"))
      (node (ref "C85") (pin "2") (pinfunction "2_2") (pintype "passive"))
      (node (ref "C86") (pin "2") (pinfunction "2_2") (pintype "passive"))
      (node (ref "C87") (pin "2") (pinfunction "2_2") (pintype "passive"))
      (node (ref "C88") (pin "2") (pinfunction "2_2") (pintype "passive"))
      (node (ref "C89") (pin "2") (pinfunction "2_2") (pintype "passive"))
      (node (ref "C9") (pin "2") (pinfunction "2_2") (pintype "passive"))
      (node (ref "C90") (pin "2") (pinfunction "2_2") (pintype "passive"))
      (node (ref "C91") (pin "1") (pinfunction "1_1") (pintype "passive"))
      (node (ref "C92") (pin "2") (pinfunction "2_2") (pintype "passive"))
      (node (ref "C93") (pin "2") (pinfunction "2_2") (pintype "passive"))
      (node (ref "GND") (pin "TP") (pinfunction "TP_TP") (pintype "input"))
      (node (ref "GND75") (pin "TP") (pinfunction "TP_TP") (pintype "input"))
      (node (ref "GND77") (pin "TP") (pinfunction "TP_TP") (pintype "input"))
      (node (ref "R12") (pin "2") (pinfunction "2_2") (pintype "passive"))
      (node (ref "R15") (pin "2") (pinfunction "2_2") (pintype "passive"))
      (node (ref "R18") (pin "2") (pinfunction "2_2") (pintype "passive"))
      (node (ref "R22") (pin "1") (pinfunction "1_1") (pintype "passive"))
      (node (ref "R2X") (pin "2") (pinfunction "2_2") (pintype "passive"))
      (node (ref "R3") (pin "2") (pinfunction "2_2") (pintype "passive"))
      (node (ref "R6") (pin "2") (pinfunction "2_2") (pintype "passive"))
      (node (ref "R9") (pin "2") (pinfunction "2_2") (pintype "passive"))
      (node (ref "SENSOR") (pin "A21") (pinfunction "GND_A21") (pintype "power_in"))
      (node (ref "SENSOR") (pin "A25") (pinfunction "GND_A25") (pintype "power_in"))
      (node (ref "SENSOR") (pin "A28") (pinfunction "GND_A28") (pintype "power_in"))
      (node (ref "SENSOR") (pin "A29") (pinfunction "GND_A29") (pintype "power_in"))
      (node (ref "SENSOR") (pin "A9") (pinfunction "GND_A9") (pintype "power_in"))
      (node (ref "SENSOR") (pin "B22") (pinfunction "GND_B22") (pintype "power_in"))
      (node (ref "SENSOR") (pin "B26") (pinfunction "GND_B26") (pintype "power_in"))
      (node (ref "SENSOR") (pin "B27") (pinfunction "GND_B27") (pintype "power_in"))
      (node (ref "SENSOR") (pin "B28") (pinfunction "GND_B28") (pintype "power_in"))
      (node (ref "SENSOR") (pin "B5") (pinfunction "GND_B5") (pintype "power_in"))
      (node (ref "SENSOR") (pin "C15") (pinfunction "GND_C15") (pintype "power_in"))
      (node (ref "SENSOR") (pin "C16") (pinfunction "GND_C16") (pintype "power_in"))
      (node (ref "SENSOR") (pin "C28") (pinfunction "GND_C28") (pintype "power_in"))
      (node (ref "SENSOR") (pin "D2") (pinfunction "GND_D2") (pintype "power_in"))
      (node (ref "SENSOR") (pin "D25") (pinfunction "GND_D25") (pintype "power_in"))
      (node (ref "SENSOR") (pin "D27") (pinfunction "GND_D27") (pintype "power_in"))
      (node (ref "SENSOR") (pin "D29") (pinfunction "GND_D29") (pintype "power_in"))
      (node (ref "SENSOR") (pin "E15") (pinfunction "GND_E15") (pintype "power_in"))
      (node (ref "SENSOR") (pin "E16") (pinfunction "GND_E16") (pintype "power_in"))
      (node (ref "SENSOR") (pin "E25") (pinfunction "GND_E25") (pintype "power_in"))
      (node (ref "SENSOR") (pin "E27") (pinfunction "GND_E27") (pintype "power_in"))
      (node (ref "SENSOR") (pin "E3") (pinfunction "GND_E3") (pintype "power_in"))
      (node (ref "SENSOR") (pin "E4") (pinfunction "DIO2_E4") (pintype "output"))
      (node (ref "SENSOR") (pin "F27") (pinfunction "GND_F27") (pintype "power_in"))
      (node (ref "SENSOR") (pin "F4") (pinfunction "DIO1_F4") (pintype "output"))
      (node (ref "SENSOR") (pin "G3") (pinfunction "DIO4_G3") (pintype "output"))
      (node (ref "SENSOR") (pin "G5") (pinfunction "GND_G5") (pintype "power_in"))
      (node (ref "SENSOR") (pin "H1") (pinfunction "GND_H1") (pintype "power_in"))
      (node (ref "SENSOR") (pin "H21") (pinfunction "GND_H21") (pintype "power_in"))
      (node (ref "SENSOR") (pin "H25") (pinfunction "GND_H25") (pintype "power_in"))
      (node (ref "SENSOR") (pin "H27") (pinfunction "GND_H27") (pintype "power_in"))
      (node (ref "SENSOR") (pin "H4") (pinfunction "DIO3_H4") (pintype "output"))
      (node (ref "SENSOR") (pin "H6") (pinfunction "GND_H6") (pintype "power_in"))
      (node (ref "SENSOR") (pin "H9") (pinfunction "GND_H9") (pintype "power_in"))
      (node (ref "U1") (pin "6") (pinfunction "ANODE_6") (pintype "input"))
      (node (ref "U2") (pin "6") (pinfunction "ANODE_6") (pintype "input"))
      (node (ref "U3") (pin "2") (pinfunction "GND_2") (pintype "power_in"))
      (node (ref "U3") (pin "EP") (pinfunction "EP_EP") (pintype "power_in"))
      (node (ref "U4") (pin "16") (pinfunction "DIR2_16") (pintype "input"))
      (node (ref "U4") (pin "7") (pinfunction "~{OE}_7") (pintype "input"))
      (node (ref "U4") (pin "8") (pinfunction "GND_8") (pintype "passive"))
      (node (ref "U5") (pin "6") (pinfunction "DIR4_6") (pintype "input"))
      (node (ref "U5") (pin "7") (pinfunction "~{OE}_7") (pintype "input"))
      (node (ref "U5") (pin "8") (pinfunction "GND_8") (pintype "passive"))
      (node (ref "U6") (pin "16") (pinfunction "DIR2_16") (pintype "input"))
      (node (ref "U6") (pin "7") (pinfunction "~{OE}_7") (pintype "input"))
      (node (ref "U6") (pin "8") (pinfunction "GND_8") (pintype "passive"))
      (node (ref "U7") (pin "4") (pinfunction "GND_4") (pintype "power_in"))
      (node (ref "U7") (pin "5") (pinfunction "A2_5") (pintype "input"))
      (node (ref "U7") (pin "6") (pinfunction "A1_6") (pintype "input"))
      (node (ref "U7") (pin "7") (pinfunction "A0_7") (pintype "input"))
      (node (ref "UEP") (pin "1") (pinfunction "A0_1") (pintype "input"))
      (node (ref "UEP") (pin "2") (pinfunction "A1_2") (pintype "input"))
      (node (ref "UEP") (pin "3") (pinfunction "A2_3") (pintype "input"))
      (node (ref "UEP") (pin "4") (pinfunction "GND_4") (pintype "passive"))
      (node (ref "UEP") (pin "EP") (pinfunction "EP_EP") (pintype "passive"))
      (node (ref "UNE") (pin "4") (pinfunction "VSS_4") (pintype "power_in"))
      (node (ref "UNE") (pin "EP") (pinfunction "EP_EP") (pintype "passive"))
      (node (ref "UNN") (pin "4") (pinfunction "VSS_4") (pintype "power_in"))
      (node (ref "UNN") (pin "EP") (pinfunction "EP_EP") (pintype "passive"))
      (node (ref "UNW") (pin "4") (pinfunction "VSS_4") (pintype "power_in"))
      (node (ref "UNW") (pin "EP") (pinfunction "EP_EP") (pintype "passive"))
      (node (ref "USE") (pin "4") (pinfunction "VSS_4") (pintype "power_in"))
      (node (ref "USE") (pin "EP") (pinfunction "EP_EP") (pintype "passive"))
      (node (ref "USS") (pin "4") (pinfunction "VSS_4") (pintype "power_in"))
      (node (ref "USS") (pin "EP") (pinfunction "EP_EP") (pintype "passive"))
      (node (ref "USW") (pin "4") (pinfunction "VSS_4") (pintype "power_in"))
      (node (ref "USW") (pin "EP") (pinfunction "EP_EP") (pintype "passive"))
      (node (ref "X-NORTH") (pin "102") (pinfunction "102_102") (pintype "bidirectional"))
      (node (ref "X-NORTH") (pin "103") (pinfunction "103_103") (pintype "bidirectional"))
      (node (ref "X-NORTH") (pin "108") (pinfunction "108_108") (pintype "bidirectional"))
      (node (ref "X-NORTH") (pin "114") (pinfunction "114_114") (pintype "bidirectional"))
      (node (ref "X-NORTH") (pin "12") (pinfunction "12_12") (pintype "bidirectional"))
      (node (ref "X-NORTH") (pin "120") (pinfunction "120_120") (pintype "bidirectional"))
      (node (ref "X-NORTH") (pin "126") (pinfunction "126_126") (pintype "bidirectional"))
      (node (ref "X-NORTH") (pin "132") (pinfunction "132_132") (pintype "bidirectional"))
      (node (ref "X-NORTH") (pin "138") (pinfunction "138_138") (pintype "bidirectional"))
      (node (ref "X-NORTH") (pin "139") (pinfunction "139_139") (pintype "bidirectional"))
      (node (ref "X-NORTH") (pin "18") (pinfunction "18_18") (pintype "bidirectional"))
      (node (ref "X-NORTH") (pin "24") (pinfunction "24_24") (pintype "bidirectional"))
      (node (ref "X-NORTH") (pin "30") (pinfunction "30_30") (pintype "bidirectional"))
      (node (ref "X-NORTH") (pin "36") (pinfunction "36_36") (pintype "bidirectional"))
      (node (ref "X-NORTH") (pin "42") (pinfunction "42_42") (pintype "bidirectional"))
      (node (ref "X-NORTH") (pin "43") (pinfunction "43_43") (pintype "bidirectional"))
      (node (ref "X-NORTH") (pin "48") (pinfunction "48_48") (pintype "bidirectional"))
      (node (ref "X-NORTH") (pin "54") (pinfunction "54_54") (pintype "bidirectional"))
      (node (ref "X-NORTH") (pin "60") (pinfunction "60_60") (pintype "bidirectional"))
      (node (ref "X-NORTH") (pin "66") (pinfunction "66_66") (pintype "bidirectional"))
      (node (ref "X-NORTH") (pin "72") (pinfunction "72_72") (pintype "bidirectional"))
      (node (ref "X-NORTH") (pin "78") (pinfunction "78_78") (pintype "bidirectional"))
      (node (ref "X-NORTH") (pin "84") (pinfunction "84_84") (pintype "bidirectional"))
      (node (ref "X-NORTH") (pin "90") (pinfunction "90_90") (pintype "bidirectional"))
      (node (ref "X-NORTH") (pin "96") (pinfunction "96_96") (pintype "bidirectional"))
      (node (ref "X-SOUTH") (pin "102") (pinfunction "102_102") (pintype "bidirectional"))
      (node (ref "X-SOUTH") (pin "103") (pinfunction "103_103") (pintype "bidirectional"))
      (node (ref "X-SOUTH") (pin "108") (pinfunction "108_108") (pintype "bidirectional"))
      (node (ref "X-SOUTH") (pin "114") (pinfunction "114_114") (pintype "bidirectional"))
      (node (ref "X-SOUTH") (pin "12") (pinfunction "12_12") (pintype "bidirectional"))
      (node (ref "X-SOUTH") (pin "120") (pinfunction "120_120") (pintype "bidirectional"))
      (node (ref "X-SOUTH") (pin "126") (pinfunction "126_126") (pintype "bidirectional"))
      (node (ref "X-SOUTH") (pin "132") (pinfunction "132_132") (pintype "bidirectional"))
      (node (ref "X-SOUTH") (pin "138") (pinfunction "138_138") (pintype "bidirectional"))
      (node (ref "X-SOUTH") (pin "139") (pinfunction "139_139") (pintype "bidirectional"))
      (node (ref "X-SOUTH") (pin "18") (pinfunction "18_18") (pintype "bidirectional"))
      (node (ref "X-SOUTH") (pin "24") (pinfunction "24_24") (pintype "bidirectional"))
      (node (ref "X-SOUTH") (pin "30") (pinfunction "30_30") (pintype "bidirectional"))
      (node (ref "X-SOUTH") (pin "36") (pinfunction "36_36") (pintype "bidirectional"))
      (node (ref "X-SOUTH") (pin "42") (pinfunction "42_42") (pintype "bidirectional"))
      (node (ref "X-SOUTH") (pin "43") (pinfunction "43_43") (pintype "bidirectional"))
      (node (ref "X-SOUTH") (pin "48") (pinfunction "48_48") (pintype "bidirectional"))
      (node (ref "X-SOUTH") (pin "54") (pinfunction "54_54") (pintype "bidirectional"))
      (node (ref "X-SOUTH") (pin "60") (pinfunction "60_60") (pintype "bidirectional"))
      (node (ref "X-SOUTH") (pin "66") (pinfunction "66_66") (pintype "bidirectional"))
      (node (ref "X-SOUTH") (pin "72") (pinfunction "72_72") (pintype "bidirectional"))
      (node (ref "X-SOUTH") (pin "78") (pinfunction "78_78") (pintype "bidirectional"))
      (node (ref "X-SOUTH") (pin "84") (pinfunction "84_84") (pintype "bidirectional"))
      (node (ref "X-SOUTH") (pin "90") (pinfunction "90_90") (pintype "bidirectional"))
      (node (ref "X-SOUTH") (pin "96") (pinfunction "96_96") (pintype "bidirectional"))
    )
    (net (code "4") (name "N$42") (class "Default")
      (node (ref "SENSOR") (pin "A2") (pinfunction "TANA_A2") (pintype "output"))
    )
    (net (code "5") (name "N00_N") (class "Default")
      (node (ref "R25") (pin "2") (pinfunction "2_2") (pintype "passive"))
      (node (ref "SENSOR") (pin "E6") (pinfunction "LVDS_CLK_P_E6") (pintype "input"))
      (node (ref "X-NORTH") (pin "16") (pinfunction "16_16") (pintype "bidirectional"))
    )
    (net (code "6") (name "N00_P") (class "Default")
      (node (ref "R25") (pin "1") (pinfunction "1_1") (pintype "passive"))
      (node (ref "SENSOR") (pin "E5") (pinfunction "LVDS_CLK_N_E5") (pintype "input"))
      (node (ref "X-NORTH") (pin "14") (pinfunction "14_14") (pintype "bidirectional"))
    )
    (net (code "7") (name "N01_N") (class "Default")
      (node (ref "SENSOR") (pin "G7") (pinfunction "OUTCLK_P_G7") (pintype "output"))
      (node (ref "X-NORTH") (pin "17") (pinfunction "17_17") (pintype "bidirectional"))
    )
    (net (code "8") (name "N01_P") (class "Default")
      (node (ref "SENSOR") (pin "G6") (pinfunction "OUTCLK_N_G6") (pintype "output"))
      (node (ref "X-NORTH") (pin "15") (pinfunction "15_15") (pintype "bidirectional"))
    )
    (net (code "9") (name "N02_N") (class "Default")
      (node (ref "SENSOR") (pin "F7") (pinfunction "OUT33_P_F7") (pintype "output"))
      (node (ref "X-NORTH") (pin "22") (pinfunction "22_22") (pintype "bidirectional"))
    )
    (net (code "10") (name "N02_P") (class "Default")
      (node (ref "SENSOR") (pin "F6") (pinfunction "OUT33_N_F6") (pintype "output"))
      (node (ref "X-NORTH") (pin "20") (pinfunction "20_20") (pintype "bidirectional"))
    )
    (net (code "11") (name "N03_N") (class "Default")
      (node (ref "X-NORTH") (pin "23") (pinfunction "23_23") (pintype "bidirectional"))
    )
    (net (code "12") (name "N03_P") (class "Default")
      (node (ref "X-NORTH") (pin "21") (pinfunction "21_21") (pintype "bidirectional"))
    )
    (net (code "13") (name "N04_N") (class "Default")
      (node (ref "SENSOR") (pin "E8") (pinfunction "OUT35_P_E8") (pintype "output"))
      (node (ref "X-NORTH") (pin "28") (pinfunction "28_28") (pintype "bidirectional"))
    )
    (net (code "14") (name "N04_P") (class "Default")
      (node (ref "SENSOR") (pin "E7") (pinfunction "OUT35_N_E7") (pintype "output"))
      (node (ref "X-NORTH") (pin "26") (pinfunction "26_26") (pintype "bidirectional"))
    )
    (net (code "15") (name "N05_N") (class "Default")
      (node (ref "SENSOR") (pin "H8") (pinfunction "OUT34_P_H8") (pintype "output"))
      (node (ref "X-NORTH") (pin "29") (pinfunction "29_29") (pintype "bidirectional"))
    )
    (net (code "16") (name "N05_P") (class "Default")
      (node (ref "SENSOR") (pin "H7") (pinfunction "OUT34_N_H7") (pintype "output"))
      (node (ref "X-NORTH") (pin "27") (pinfunction "27_27") (pintype "bidirectional"))
    )
    (net (code "17") (name "N06_N") (class "Default")
      (node (ref "SENSOR") (pin "F9") (pinfunction "OUT37_P_F9") (pintype "output"))
      (node (ref "X-NORTH") (pin "34") (pinfunction "34_34") (pintype "bidirectional"))
    )
    (net (code "18") (name "N06_P") (class "Default")
      (node (ref "SENSOR") (pin "F8") (pinfunction "OUT37_N_F8") (pintype "output"))
      (node (ref "X-NORTH") (pin "32") (pinfunction "32_32") (pintype "bidirectional"))
    )
    (net (code "19") (name "N07_N") (class "Default")
      (node (ref "SENSOR") (pin "G9") (pinfunction "OUT36_P_G9") (pintype "output"))
      (node (ref "X-NORTH") (pin "35") (pinfunction "35_35") (pintype "bidirectional"))
    )
    (net (code "20") (name "N07_P") (class "Default")
      (node (ref "SENSOR") (pin "G8") (pinfunction "OUT36_N_G8") (pintype "output"))
      (node (ref "X-NORTH") (pin "33") (pinfunction "33_33") (pintype "bidirectional"))
    )
    (net (code "21") (name "N08_N") (class "Default")
      (node (ref "SENSOR") (pin "E10") (pinfunction "OUT38_P_E10") (pintype "output"))
      (node (ref "X-NORTH") (pin "40") (pinfunction "40_40") (pintype "bidirectional"))
    )
    (net (code "22") (name "N08_P") (class "Default")
      (node (ref "SENSOR") (pin "E9") (pinfunction "OUT38_N_E9") (pintype "output"))
      (node (ref "X-NORTH") (pin "38") (pinfunction "38_38") (pintype "bidirectional"))
    )
    (net (code "23") (name "N09_N") (class "Default")
      (node (ref "SENSOR") (pin "G11") (pinfunction "OUT39_P_G11") (pintype "output"))
      (node (ref "X-NORTH") (pin "41") (pinfunction "41_41") (pintype "bidirectional"))
    )
    (net (code "24") (name "N09_P") (class "Default")
      (node (ref "SENSOR") (pin "G10") (pinfunction "OUT39_N_G10") (pintype "output"))
      (node (ref "X-NORTH") (pin "39") (pinfunction "39_39") (pintype "bidirectional"))
    )
    (net (code "25") (name "N10_N") (class "Default")
      (node (ref "SENSOR") (pin "F11") (pinfunction "OUT40_P_F11") (pintype "output"))
      (node (ref "X-NORTH") (pin "46") (pinfunction "46_46") (pintype "bidirectional"))
    )
    (net (code "26") (name "N10_P") (class "Default")
      (node (ref "SENSOR") (pin "F10") (pinfunction "OUT40_N_F10") (pintype "output"))
      (node (ref "X-NORTH") (pin "44") (pinfunction "44_44") (pintype "bidirectional"))
    )
    (net (code "27") (name "N11_N") (class "Default")
      (node (ref "SENSOR") (pin "H12") (pinfunction "OUT41_P_H12") (pintype "output"))
      (node (ref "X-NORTH") (pin "47") (pinfunction "47_47") (pintype "bidirectional"))
    )
    (net (code "28") (name "N11_P") (class "Default")
      (node (ref "SENSOR") (pin "H11") (pinfunction "OUT41_N_H11") (pintype "output"))
      (node (ref "X-NORTH") (pin "45") (pinfunction "45_45") (pintype "bidirectional"))
    )
    (net (code "29") (name "N12_N") (class "Default")
      (node (ref "SENSOR") (pin "E12") (pinfunction "OUT42_P_E12") (pintype "output"))
      (node (ref "X-NORTH") (pin "52") (pinfunction "52_52") (pintype "bidirectional"))
    )
    (net (code "30") (name "N12_P") (class "Default")
      (node (ref "SENSOR") (pin "E11") (pinfunction "OUT42_N_E11") (pintype "output"))
      (node (ref "X-NORTH") (pin "50") (pinfunction "50_50") (pintype "bidirectional"))
    )
    (net (code "31") (name "N13_N") (class "Default")
      (node (ref "SENSOR") (pin "G13") (pinfunction "OUT43_P_G13") (pintype "output"))
      (node (ref "X-NORTH") (pin "53") (pinfunction "53_53") (pintype "bidirectional"))
    )
    (net (code "32") (name "N13_P") (class "Default")
      (node (ref "SENSOR") (pin "G12") (pinfunction "OUT43_N_G12") (pintype "output"))
      (node (ref "X-NORTH") (pin "51") (pinfunction "51_51") (pintype "bidirectional"))
    )
    (net (code "33") (name "N14_N") (class "Default")
      (node (ref "SENSOR") (pin "F13") (pinfunction "OUT44_P_F13") (pintype "output"))
      (node (ref "X-NORTH") (pin "58") (pinfunction "58_58") (pintype "bidirectional"))
    )
    (net (code "34") (name "N14_P") (class "Default")
      (node (ref "SENSOR") (pin "F12") (pinfunction "OUT44_N_F12") (pintype "output"))
      (node (ref "X-NORTH") (pin "56") (pinfunction "56_56") (pintype "bidirectional"))
    )
    (net (code "35") (name "N15_N") (class "Default")
      (node (ref "SENSOR") (pin "H14") (pinfunction "OUT45_P_H14") (pintype "output"))
      (node (ref "X-NORTH") (pin "59") (pinfunction "59_59") (pintype "bidirectional"))
    )
    (net (code "36") (name "N15_P") (class "Default")
      (node (ref "SENSOR") (pin "H13") (pinfunction "OUT45_N_H13") (pintype "output"))
      (node (ref "X-NORTH") (pin "57") (pinfunction "57_57") (pintype "bidirectional"))
    )
    (net (code "37") (name "N16_N") (class "Default")
      (node (ref "SENSOR") (pin "E14") (pinfunction "OUT46_P_E14") (pintype "output"))
      (node (ref "X-NORTH") (pin "64") (pinfunction "64_64") (pintype "bidirectional"))
    )
    (net (code "38") (name "N16_P") (class "Default")
      (node (ref "SENSOR") (pin "E13") (pinfunction "OUT46_N_E13") (pintype "output"))
      (node (ref "X-NORTH") (pin "62") (pinfunction "62_62") (pintype "bidirectional"))
    )
    (net (code "39") (name "N17_N") (class "Default")
      (node (ref "SENSOR") (pin "G15") (pinfunction "OUT47_P_G15") (pintype "output"))
      (node (ref "X-NORTH") (pin "65") (pinfunction "65_65") (pintype "bidirectional"))
    )
    (net (code "40") (name "N17_P") (class "Default")
      (node (ref "SENSOR") (pin "G14") (pinfunction "OUT47_N_G14") (pintype "output"))
      (node (ref "X-NORTH") (pin "63") (pinfunction "63_63") (pintype "bidirectional"))
    )
    (net (code "41") (name "N18_N") (class "Default")
      (node (ref "SENSOR") (pin "F15") (pinfunction "OUT48_P_F15") (pintype "output"))
      (node (ref "X-NORTH") (pin "70") (pinfunction "70_70") (pintype "bidirectional"))
    )
    (net (code "42") (name "N18_P") (class "Default")
      (node (ref "SENSOR") (pin "F14") (pinfunction "OUT48_N_F14") (pintype "output"))
      (node (ref "X-NORTH") (pin "68") (pinfunction "68_68") (pintype "bidirectional"))
    )
    (net (code "43") (name "N19_N") (class "Default")
      (node (ref "SENSOR") (pin "G17") (pinfunction "OUT50_P_G17") (pintype "output"))
      (node (ref "X-NORTH") (pin "71") (pinfunction "71_71") (pintype "bidirectional"))
    )
    (net (code "44") (name "N19_P") (class "Default")
      (node (ref "SENSOR") (pin "G16") (pinfunction "OUT50_N_G16") (pintype "output"))
      (node (ref "X-NORTH") (pin "69") (pinfunction "69_69") (pintype "bidirectional"))
    )
    (net (code "45") (name "N20_N") (class "Default")
      (node (ref "SENSOR") (pin "F17") (pinfunction "OUT49_P_F17") (pintype "output"))
      (node (ref "X-NORTH") (pin "76") (pinfunction "76_76") (pintype "bidirectional"))
    )
    (net (code "46") (name "N20_P") (class "Default")
      (node (ref "SENSOR") (pin "F16") (pinfunction "OUT49_N_F16") (pintype "output"))
      (node (ref "X-NORTH") (pin "74") (pinfunction "74_74") (pintype "bidirectional"))
    )
    (net (code "47") (name "N21_N") (class "Default")
      (node (ref "SENSOR") (pin "H18") (pinfunction "OUT52_P_H18") (pintype "output"))
      (node (ref "X-NORTH") (pin "77") (pinfunction "77_77") (pintype "bidirectional"))
    )
    (net (code "48") (name "N21_P") (class "Default")
      (node (ref "SENSOR") (pin "H17") (pinfunction "OUT52_N_H17") (pintype "output"))
      (node (ref "X-NORTH") (pin "75") (pinfunction "75_75") (pintype "bidirectional"))
    )
    (net (code "49") (name "N22_N") (class "Default")
      (node (ref "SENSOR") (pin "E18") (pinfunction "OUT51_P_E18") (pintype "output"))
      (node (ref "X-NORTH") (pin "82") (pinfunction "82_82") (pintype "bidirectional"))
    )
    (net (code "50") (name "N22_P") (class "Default")
      (node (ref "SENSOR") (pin "E17") (pinfunction "OUT51_N_E17") (pintype "output"))
      (node (ref "X-NORTH") (pin "80") (pinfunction "80_80") (pintype "bidirectional"))
    )
    (net (code "51") (name "N23_N") (class "Default")
      (node (ref "SENSOR") (pin "G19") (pinfunction "OUT54_P_G19") (pintype "output"))
      (node (ref "X-NORTH") (pin "83") (pinfunction "83_83") (pintype "bidirectional"))
    )
    (net (code "52") (name "N23_P") (class "Default")
      (node (ref "SENSOR") (pin "G18") (pinfunction "OUT54_N_G18") (pintype "output"))
      (node (ref "X-NORTH") (pin "81") (pinfunction "81_81") (pintype "bidirectional"))
    )
    (net (code "53") (name "N24_N") (class "Default")
      (node (ref "SENSOR") (pin "F19") (pinfunction "OUT53_P_F19") (pintype "output"))
      (node (ref "X-NORTH") (pin "88") (pinfunction "88_88") (pintype "bidirectional"))
    )
    (net (code "54") (name "N24_P") (class "Default")
      (node (ref "SENSOR") (pin "F18") (pinfunction "OUT53_N_F18") (pintype "output"))
      (node (ref "X-NORTH") (pin "86") (pinfunction "86_86") (pintype "bidirectional"))
    )
    (net (code "55") (name "N25_N") (class "Default")
      (node (ref "SENSOR") (pin "H20") (pinfunction "OUT56_P_H20") (pintype "output"))
      (node (ref "X-NORTH") (pin "89") (pinfunction "89_89") (pintype "bidirectional"))
    )
    (net (code "56") (name "N25_P") (class "Default")
      (node (ref "SENSOR") (pin "H19") (pinfunction "OUT56_N_H19") (pintype "output"))
      (node (ref "X-NORTH") (pin "87") (pinfunction "87_87") (pintype "bidirectional"))
    )
    (net (code "57") (name "N26_N") (class "Default")
      (node (ref "SENSOR") (pin "E20") (pinfunction "OUT55_P_E20") (pintype "output"))
      (node (ref "X-NORTH") (pin "94") (pinfunction "94_94") (pintype "bidirectional"))
    )
    (net (code "58") (name "N26_P") (class "Default")
      (node (ref "SENSOR") (pin "E19") (pinfunction "OUT55_N_E19") (pintype "output"))
      (node (ref "X-NORTH") (pin "92") (pinfunction "92_92") (pintype "bidirectional"))
    )
    (net (code "59") (name "N27_N") (class "Default")
      (node (ref "SENSOR") (pin "G21") (pinfunction "OUT58_P_G21") (pintype "output"))
      (node (ref "X-NORTH") (pin "95") (pinfunction "95_95") (pintype "bidirectional"))
    )
    (net (code "60") (name "N27_P") (class "Default")
      (node (ref "SENSOR") (pin "G20") (pinfunction "OUT58_N_G20") (pintype "output"))
      (node (ref "X-NORTH") (pin "93") (pinfunction "93_93") (pintype "bidirectional"))
    )
    (net (code "61") (name "N28_N") (class "Default")
      (node (ref "SENSOR") (pin "F21") (pinfunction "OUT57_P_F21") (pintype "output"))
      (node (ref "X-NORTH") (pin "100") (pinfunction "100_100") (pintype "bidirectional"))
    )
    (net (code "62") (name "N28_P") (class "Default")
      (node (ref "SENSOR") (pin "F20") (pinfunction "OUT57_N_F20") (pintype "output"))
      (node (ref "X-NORTH") (pin "98") (pinfunction "98_98") (pintype "bidirectional"))
    )
    (net (code "63") (name "N29_N") (class "Default")
      (node (ref "SENSOR") (pin "G23") (pinfunction "OUT61_P_G23") (pintype "output"))
      (node (ref "X-NORTH") (pin "101") (pinfunction "101_101") (pintype "bidirectional"))
    )
    (net (code "64") (name "N29_P") (class "Default")
      (node (ref "SENSOR") (pin "G22") (pinfunction "OUT61_N_G22") (pintype "output"))
      (node (ref "X-NORTH") (pin "99") (pinfunction "99_99") (pintype "bidirectional"))
    )
    (net (code "65") (name "N30_N") (class "Default")
      (node (ref "SENSOR") (pin "E22") (pinfunction "OUT59_P_E22") (pintype "output"))
      (node (ref "X-NORTH") (pin "106") (pinfunction "106_106") (pintype "bidirectional"))
    )
    (net (code "66") (name "N30_P") (class "Default")
      (node (ref "SENSOR") (pin "E21") (pinfunction "OUT59_N_E21") (pintype "output"))
      (node (ref "X-NORTH") (pin "104") (pinfunction "104_104") (pintype "bidirectional"))
    )
    (net (code "67") (name "N31_N") (class "Default")
      (node (ref "SENSOR") (pin "H24") (pinfunction "OUT63_P_H24") (pintype "output"))
      (node (ref "X-NORTH") (pin "107") (pinfunction "107_107") (pintype "bidirectional"))
    )
    (net (code "68") (name "N31_P") (class "Default")
      (node (ref "SENSOR") (pin "H23") (pinfunction "OUT63_N_H23") (pintype "output"))
      (node (ref "X-NORTH") (pin "105") (pinfunction "105_105") (pintype "bidirectional"))
    )
    (net (code "69") (name "N32_N") (class "Default")
      (node (ref "SENSOR") (pin "F23") (pinfunction "OUT60_P_F23") (pintype "output"))
      (node (ref "X-NORTH") (pin "112") (pinfunction "112_112") (pintype "bidirectional"))
    )
    (net (code "70") (name "N32_P") (class "Default")
      (node (ref "SENSOR") (pin "F22") (pinfunction "OUT60_N_F22") (pintype "output"))
      (node (ref "X-NORTH") (pin "110") (pinfunction "110_110") (pintype "bidirectional"))
    )
    (net (code "71") (name "N33_N") (class "Default")
      (node (ref "SENSOR") (pin "G25") (pinfunction "OUT64_P_G25") (pintype "output"))
      (node (ref "X-NORTH") (pin "113") (pinfunction "113_113") (pintype "bidirectional"))
    )
    (net (code "72") (name "N33_P") (class "Default")
      (node (ref "SENSOR") (pin "G24") (pinfunction "OUT64_N_G24") (pintype "output"))
      (node (ref "X-NORTH") (pin "111") (pinfunction "111_111") (pintype "bidirectional"))
    )
    (net (code "73") (name "N34_N") (class "Default")
      (node (ref "SENSOR") (pin "E24") (pinfunction "OUT62_P_E24") (pintype "output"))
      (node (ref "X-NORTH") (pin "118") (pinfunction "118_118") (pintype "bidirectional"))
    )
    (net (code "74") (name "N34_P") (class "Default")
      (node (ref "SENSOR") (pin "E23") (pinfunction "OUT62_N_E23") (pintype "output"))
      (node (ref "X-NORTH") (pin "116") (pinfunction "116_116") (pintype "bidirectional"))
    )
    (net (code "75") (name "N35_N") (class "Default")
      (node (ref "U6") (pin "4") (pinfunction "A4_4") (pintype "bidirectional"))
      (node (ref "X-NORTH") (pin "119") (pinfunction "119_119") (pintype "bidirectional"))
    )
    (net (code "76") (name "N35_P") (class "Default")
      (node (ref "U6") (pin "3") (pinfunction "A3_3") (pintype "bidirectional"))
      (node (ref "X-NORTH") (pin "117") (pinfunction "117_117") (pintype "bidirectional"))
    )
    (net (code "77") (name "N36_N") (class "Default")
      (node (ref "X-NORTH") (pin "124") (pinfunction "124_124") (pintype "bidirectional"))
    )
    (net (code "78") (name "N36_P") (class "Default")
      (node (ref "X-NORTH") (pin "122") (pinfunction "122_122") (pintype "bidirectional"))
    )
    (net (code "79") (name "N37_N") (class "Default")
      (node (ref "U5") (pin "3") (pinfunction "A3_3") (pintype "bidirectional"))
      (node (ref "X-NORTH") (pin "125") (pinfunction "125_125") (pintype "bidirectional"))
    )
    (net (code "80") (name "N37_P") (class "Default")
      (node (ref "U5") (pin "4") (pinfunction "A4_4") (pintype "bidirectional"))
      (node (ref "X-NORTH") (pin "123") (pinfunction "123_123") (pintype "bidirectional"))
    )
    (net (code "81") (name "N38_N") (class "Default")
      (node (ref "U6") (pin "2") (pinfunction "A2_2") (pintype "bidirectional"))
      (node (ref "X-NORTH") (pin "130") (pinfunction "130_130") (pintype "bidirectional"))
    )
    (net (code "82") (name "N38_P") (class "Default")
      (node (ref "U6") (pin "1") (pinfunction "A1_1") (pintype "bidirectional"))
      (node (ref "X-NORTH") (pin "128") (pinfunction "128_128") (pintype "bidirectional"))
    )
    (net (code "83") (name "N39_N") (class "Default")
      (node (ref "U5") (pin "1") (pinfunction "A1_1") (pintype "bidirectional"))
      (node (ref "X-NORTH") (pin "131") (pinfunction "131_131") (pintype "bidirectional"))
    )
    (net (code "84") (name "N39_P") (class "Default")
      (node (ref "U5") (pin "2") (pinfunction "A2_2") (pintype "bidirectional"))
      (node (ref "X-NORTH") (pin "129") (pinfunction "129_129") (pintype "bidirectional"))
    )
    (net (code "85") (name "N_CHK_EN") (class "Default")
      (node (ref "X-NORTH") (pin "8") (pinfunction "8_8") (pintype "bidirectional"))
    )
    (net (code "86") (name "N_CHK_V") (class "Default")
      (node (ref "C2") (pin "1") (pinfunction "1_1") (pintype "passive"))
      (node (ref "C3") (pin "1") (pinfunction "1_1") (pintype "passive"))
      (node (ref "C4") (pin "1") (pinfunction "1_1") (pintype "passive"))
      (node (ref "R19") (pin "1") (pinfunction "1_1") (pintype "passive"))
      (node (ref "TP1") (pin "TP") (pinfunction "TP_TP") (pintype "input"))
      (node (ref "UNE") (pin "8") (pinfunction "VDD_8") (pintype "power_in"))
      (node (ref "UNN") (pin "8") (pinfunction "VDD_8") (pintype "power_in"))
      (node (ref "UNW") (pin "8") (pinfunction "VDD_8") (pintype "power_in"))
      (node (ref "X-NORTH") (pin "10") (pinfunction "10_10") (pintype "bidirectional"))
    )
    (net (code "87") (name "N_I2C_EN") (class "Default")
      (node (ref "X-NORTH") (pin "137") (pinfunction "137_137") (pintype "bidirectional"))
    )
    (net (code "88") (name "N_I2C_V") (class "Default")
      (node (ref "C1") (pin "1") (pinfunction "1_1") (pintype "passive"))
      (node (ref "R1X") (pin "1") (pinfunction "1_1") (pintype "passive"))
      (node (ref "UEP") (pin "8") (pinfunction "VCC_8") (pintype "power_in"))
      (node (ref "X-NORTH") (pin "135") (pinfunction "135_135") (pintype "bidirectional"))
    )
    (net (code "89") (name "N_REF") (class "Default")
      (node (ref "R19") (pin "2") (pinfunction "2_2") (pintype "passive"))
      (node (ref "TP2") (pin "TP") (pinfunction "TP_TP") (pintype "input"))
      (node (ref "U1") (pin "1") (pinfunction "CATHODE_1") (pintype "output"))
      (node (ref "U1") (pin "3") (pinfunction "REF_3") (pintype "input"))
      (node (ref "UNE") (pin "2") (pinfunction "VINA-_2") (pintype "input"))
      (node (ref "UNE") (pin "5") (pinfunction "VINB+_5") (pintype "input"))
      (node (ref "UNN") (pin "2") (pinfunction "VINA-_2") (pintype "input"))
      (node (ref "UNN") (pin "5") (pinfunction "VINB+_5") (pintype "input"))
      (node (ref "UNW") (pin "2") (pinfunction "VINA-_2") (pintype "input"))
      (node (ref "UNW") (pin "5") (pinfunction "VINB+_5") (pintype "input"))
    )
    (net (code "90") (name "N_SCK") (class "Default")
      (node (ref "U4") (pin "4") (pinfunction "A4_4") (pintype "bidirectional"))
      (node (ref "X-NORTH") (pin "144") (pinfunction "144_144") (pintype "bidirectional"))
    )
    (net (code "91") (name "N_SCL") (class "Default")
      (node (ref "UEP") (pin "6") (pinfunction "SCL_6") (pintype "input"))
      (node (ref "X-NORTH") (pin "143") (pinfunction "143_143") (pintype "bidirectional"))
    )
    (net (code "92") (name "N_SDA") (class "Default")
      (node (ref "UEP") (pin "5") (pinfunction "SDA_5") (pintype "bidirectional"))
      (node (ref "X-NORTH") (pin "141") (pinfunction "141_141") (pintype "bidirectional"))
    )
    (net (code "93") (name "N_SDI") (class "Default")
      (node (ref "U4") (pin "2") (pinfunction "A2_2") (pintype "bidirectional"))
      (node (ref "X-NORTH") (pin "140") (pinfunction "140_140") (pintype "bidirectional"))
    )
    (net (code "94") (name "N_SDO") (class "Default")
      (node (ref "U4") (pin "3") (pinfunction "A3_3") (pintype "bidirectional"))
      (node (ref "X-NORTH") (pin "142") (pinfunction "142_142") (pintype "bidirectional"))
    )
    (net (code "95") (name "N_SPI_EN") (class "Default")
      (node (ref "U4") (pin "1") (pinfunction "A1_1") (pintype "bidirectional"))
      (node (ref "X-NORTH") (pin "136") (pinfunction "136_136") (pintype "bidirectional"))
    )
    (net (code "96") (name "N_SPI_V") (class "Default")
      (node (ref "C59") (pin "1") (pinfunction "1_1") (pintype "passive"))
      (node (ref "U4") (pin "14") (pinfunction "VCCA_14") (pintype "power_in"))
      (node (ref "U4") (pin "15") (pinfunction "DIR1_15") (pintype "input"))
      (node (ref "U4") (pin "5") (pinfunction "DIR3_5") (pintype "input"))
      (node (ref "U4") (pin "6") (pinfunction "DIR4_6") (pintype "input"))
      (node (ref "X-NORTH") (pin "134") (pinfunction "134_134") (pintype "bidirectional"))
    )
    (net (code "97") (name "N_VE") (class "Default")
      (node (ref "C22") (pin "1") (pinfunction "1_1") (pintype "passive"))
      (node (ref "C23") (pin "1") (pinfunction "1_1") (pintype "passive"))
      (node (ref "C24") (pin "1") (pinfunction "1_1") (pintype "passive"))
      (node (ref "C25") (pin "1") (pinfunction "1_1") (pintype "passive"))
      (node (ref "C26") (pin "1") (pinfunction "1_1") (pintype "passive"))
      (node (ref "C27") (pin "1") (pinfunction "1_1") (pintype "passive"))
      (node (ref "C28") (pin "1") (pinfunction "1_1") (pintype "passive"))
      (node (ref "C50") (pin "1") (pinfunction "1_1") (pintype "passive"))
      (node (ref "C51") (pin "1") (pinfunction "1_1") (pintype "passive"))
      (node (ref "C52") (pin "1") (pinfunction "1_1") (pintype "passive"))
      (node (ref "C53") (pin "1") (pinfunction "1_1") (pintype "passive"))
      (node (ref "C54") (pin "1") (pinfunction "1_1") (pintype "passive"))
      (node (ref "C55") (pin "1") (pinfunction "1_1") (pintype "passive"))
      (node (ref "C56") (pin "1") (pinfunction "1_1") (pintype "passive"))
      (node (ref "C67") (pin "1") (pinfunction "1_1") (pintype "passive"))
      (node (ref "C69") (pin "1") (pinfunction "1_1") (pintype "passive"))
      (node (ref "C75") (pin "1") (pinfunction "1_1") (pintype "passive"))
      (node (ref "C76") (pin "1") (pinfunction "1_1") (pintype "passive"))
      (node (ref "C77") (pin "1") (pinfunction "1_1") (pintype "passive"))
      (node (ref "C84") (pin "1") (pinfunction "1_1") (pintype "passive"))
      (node (ref "C85") (pin "1") (pinfunction "1_1") (pintype "passive"))
      (node (ref "C86") (pin "1") (pinfunction "1_1") (pintype "passive"))
      (node (ref "C93") (pin "1") (pinfunction "1_1") (pintype "passive"))
      (node (ref "SENSOR") (pin "C26") (pinfunction "VDD33_C26") (pintype "power_in"))
      (node (ref "SENSOR") (pin "C27") (pinfunction "VDD33_C27") (pintype "power_in"))
      (node (ref "SENSOR") (pin "D26") (pinfunction "VDD33_D26") (pintype "power_in"))
      (node (ref "SENSOR") (pin "D3") (pinfunction "VDD33_D3") (pintype "power_in"))
      (node (ref "SENSOR") (pin "E26") (pinfunction "VDD33_E26") (pintype "power_in"))
      (node (ref "SENSOR") (pin "F26") (pinfunction "VDD33_F26") (pintype "power_in"))
      (node (ref "SENSOR") (pin "F5") (pinfunction "VDD33_F5") (pintype "power_in"))
      (node (ref "TP7") (pin "TP") (pinfunction "TP_TP") (pintype "input"))
      (node (ref "U4") (pin "13") (pinfunction "VCCB_13") (pintype "power_in"))
      (node (ref "U5") (pin "13") (pinfunction "VCCB_13") (pintype "power_in"))
      (node (ref "U6") (pin "13") (pinfunction "VCCB_13") (pintype "power_in"))
      (node (ref "X-NORTH") (pin "109") (pinfunction "109_109") (pintype "bidirectional"))
      (node (ref "X-NORTH") (pin "115") (pinfunction "115_115") (pintype "bidirectional"))
      (node (ref "X-NORTH") (pin "121") (pinfunction "121_121") (pintype "bidirectional"))
      (node (ref "X-NORTH") (pin "127") (pinfunction "127_127") (pintype "bidirectional"))
      (node (ref "X-NORTH") (pin "133") (pinfunction "133_133") (pintype "bidirectional"))
    )
    (net (code "98") (name "N_VE_CV") (class "Default")
      (node (ref "C10") (pin "1") (pinfunction "1_1") (pintype "passive"))
      (node (ref "R7") (pin "1") (pinfunction "1_1") (pintype "passive"))
      (node (ref "X-NORTH") (pin "6") (pinfunction "6_6") (pintype "bidirectional"))
    )
    (net (code "99") (name "N_VE_OV") (class "Default")
      (node (ref "UNE") (pin "7") (pinfunction "OUTB_7") (pintype "output"))
      (node (ref "X-NORTH") (pin "5") (pinfunction "5_5") (pintype "bidirectional"))
    )
    (net (code "100") (name "N_VE_UV") (class "Default")
      (node (ref "UNE") (pin "1") (pinfunction "OUTA_1") (pintype "output"))
      (node (ref "X-NORTH") (pin "11") (pinfunction "11_11") (pintype "bidirectional"))
    )
    (net (code "101") (name "N_VN") (class "Default")
      (node (ref "C31") (pin "1") (pinfunction "1_1") (pintype "passive"))
      (node (ref "C32") (pin "1") (pinfunction "1_1") (pintype "passive"))
      (node (ref "C33") (pin "1") (pinfunction "1_1") (pintype "passive"))
      (node (ref "C34") (pin "1") (pinfunction "1_1") (pintype "passive"))
      (node (ref "C35") (pin "1") (pinfunction "1_1") (pintype "passive"))
      (node (ref "C36") (pin "1") (pinfunction "1_1") (pintype "passive"))
      (node (ref "C37") (pin "1") (pinfunction "1_1") (pintype "passive"))
      (node (ref "C38") (pin "1") (pinfunction "1_1") (pintype "passive"))
      (node (ref "C39") (pin "1") (pinfunction "1_1") (pintype "passive"))
      (node (ref "C40") (pin "1") (pinfunction "1_1") (pintype "passive"))
      (node (ref "C41") (pin "1") (pinfunction "1_1") (pintype "passive"))
      (node (ref "C42") (pin "1") (pinfunction "1_1") (pintype "passive"))
      (node (ref "C43") (pin "1") (pinfunction "1_1") (pintype "passive"))
      (node (ref "C44") (pin "1") (pinfunction "1_1") (pintype "passive"))
      (node (ref "C68") (pin "1") (pinfunction "1_1") (pintype "passive"))
      (node (ref "C70") (pin "1") (pinfunction "1_1") (pintype "passive"))
      (node (ref "C78") (pin "1") (pinfunction "1_1") (pintype "passive"))
      (node (ref "C79") (pin "1") (pinfunction "1_1") (pintype "passive"))
      (node (ref "C80") (pin "1") (pinfunction "1_1") (pintype "passive"))
      (node (ref "C87") (pin "1") (pinfunction "1_1") (pintype "passive"))
      (node (ref "C88") (pin "1") (pinfunction "1_1") (pintype "passive"))
      (node (ref "C89") (pin "1") (pinfunction "1_1") (pintype "passive"))
      (node (ref "SENSOR") (pin "A10") (pinfunction "VDD18_A10") (pintype "power_in"))
      (node (ref "SENSOR") (pin "A15") (pinfunction "VDD18_A15") (pintype "power_in"))
      (node (ref "SENSOR") (pin "A16") (pinfunction "VDD18_A16") (pintype "power_in"))
      (node (ref "SENSOR") (pin "A22") (pinfunction "VDD18_A22") (pintype "power_in"))
      (node (ref "SENSOR") (pin "A26") (pinfunction "VDD18_A26") (pintype "power_in"))
      (node (ref "SENSOR") (pin "A27") (pinfunction "VDD18_A27") (pintype "power_in"))
      (node (ref "SENSOR") (pin "B4") (pinfunction "VDD18_B4") (pintype "power_in"))
      (node (ref "SENSOR") (pin "E1") (pinfunction "VDD18_PLL_E1") (pintype "power_in"))
      (node (ref "SENSOR") (pin "H10") (pinfunction "VDD18_H10") (pintype "power_in"))
      (node (ref "SENSOR") (pin "H15") (pinfunction "VDD18_H15") (pintype "power_in"))
      (node (ref "SENSOR") (pin "H16") (pinfunction "VDD18_H16") (pintype "power_in"))
      (node (ref "SENSOR") (pin "H22") (pinfunction "VDD18_H22") (pintype "power_in"))
      (node (ref "SENSOR") (pin "H26") (pinfunction "VDD18_H26") (pintype "power_in"))
      (node (ref "SENSOR") (pin "H5") (pinfunction "VDD18_H5") (pintype "power_in"))
      (node (ref "TP5") (pin "TP") (pinfunction "TP_TP") (pintype "input"))
      (node (ref "U5") (pin "14") (pinfunction "VCCA_14") (pintype "power_in"))
      (node (ref "U5") (pin "15") (pinfunction "DIR1_15") (pintype "input"))
      (node (ref "U5") (pin "16") (pinfunction "DIR2_16") (pintype "input"))
      (node (ref "U5") (pin "5") (pinfunction "DIR3_5") (pintype "input"))
      (node (ref "U6") (pin "14") (pinfunction "VCCA_14") (pintype "power_in"))
      (node (ref "U6") (pin "15") (pinfunction "DIR1_15") (pintype "input"))
      (node (ref "U6") (pin "5") (pinfunction "DIR3_5") (pintype "input"))
      (node (ref "U6") (pin "6") (pinfunction "DIR4_6") (pintype "input"))
      (node (ref "X-NORTH") (pin "49") (pinfunction "49_49") (pintype "bidirectional"))
      (node (ref "X-NORTH") (pin "55") (pinfunction "55_55") (pintype "bidirectional"))
      (node (ref "X-NORTH") (pin "61") (pinfunction "61_61") (pintype "bidirectional"))
      (node (ref "X-NORTH") (pin "67") (pinfunction "67_67") (pintype "bidirectional"))
      (node (ref "X-NORTH") (pin "73") (pinfunction "73_73") (pintype "bidirectional"))
      (node (ref "X-NORTH") (pin "79") (pinfunction "79_79") (pintype "bidirectional"))
      (node (ref "X-NORTH") (pin "85") (pinfunction "85_85") (pintype "bidirectional"))
      (node (ref "X-NORTH") (pin "91") (pinfunction "91_91") (pintype "bidirectional"))
      (node (ref "X-NORTH") (pin "97") (pinfunction "97_97") (pintype "bidirectional"))
    )
    (net (code "102") (name "N_VN_CV") (class "Default")
      (node (ref "C9") (pin "1") (pinfunction "1_1") (pintype "passive"))
      (node (ref "R4") (pin "1") (pinfunction "1_1") (pintype "passive"))
      (node (ref "X-NORTH") (pin "4") (pinfunction "4_4") (pintype "bidirectional"))
    )
    (net (code "103") (name "N_VN_OV") (class "Default")
      (node (ref "UNN") (pin "7") (pinfunction "OUTB_7") (pintype "output"))
      (node (ref "X-NORTH") (pin "3") (pinfunction "3_3") (pintype "bidirectional"))
    )
    (net (code "104") (name "N_VN_UV") (class "Default")
      (node (ref "UNN") (pin "1") (pinfunction "OUTA_1") (pintype "output"))
      (node (ref "X-NORTH") (pin "9") (pinfunction "9_9") (pintype "bidirectional"))
    )
    (net (code "105") (name "N_VW") (class "Default")
      (node (ref "C57") (pin "1") (pinfunction "1_1") (pintype "passive"))
      (node (ref "C58") (pin "1") (pinfunction "1_1") (pintype "passive"))
      (node (ref "C92") (pin "1") (pinfunction "1_1") (pintype "passive"))
      (node (ref "SENSOR") (pin "E2") (pinfunction "VDD_RES_E2") (pintype "power_in"))
      (node (ref "SENSOR") (pin "G4") (pinfunction "VDD_RES_G4") (pintype "power_in"))
      (node (ref "TP8") (pin "TP") (pinfunction "TP_TP") (pintype "input"))
      (node (ref "X-NORTH") (pin "13") (pinfunction "13_13") (pintype "bidirectional"))
      (node (ref "X-NORTH") (pin "19") (pinfunction "19_19") (pintype "bidirectional"))
      (node (ref "X-NORTH") (pin "25") (pinfunction "25_25") (pintype "bidirectional"))
      (node (ref "X-NORTH") (pin "31") (pinfunction "31_31") (pintype "bidirectional"))
      (node (ref "X-NORTH") (pin "37") (pinfunction "37_37") (pintype "bidirectional"))
    )
    (net (code "106") (name "N_VW_CV") (class "Default")
      (node (ref "C8") (pin "1") (pinfunction "1_1") (pintype "passive"))
      (node (ref "R1") (pin "1") (pinfunction "1_1") (pintype "passive"))
      (node (ref "X-NORTH") (pin "2") (pinfunction "2_2") (pintype "bidirectional"))
    )
    (net (code "107") (name "N_VW_OV") (class "Default")
      (node (ref "UNW") (pin "7") (pinfunction "OUTB_7") (pintype "output"))
      (node (ref "X-NORTH") (pin "1") (pinfunction "1_1") (pintype "bidirectional"))
    )
    (net (code "108") (name "N_VW_UV") (class "Default")
      (node (ref "UNW") (pin "1") (pinfunction "OUTA_1") (pintype "output"))
      (node (ref "X-NORTH") (pin "7") (pinfunction "7_7") (pintype "bidirectional"))
    )
    (net (code "109") (name "Net-(SENSORB-CMDN)") (class "Default")
      (node (ref "C61") (pin "1") (pinfunction "1_1") (pintype "passive"))
      (node (ref "SENSOR") (pin "F1") (pinfunction "CMDN_F1") (pintype "bidirectional"))
    )
    (net (code "110") (name "Net-(SENSORB-CMDP)") (class "Default")
      (node (ref "C22") (pin "2") (pinfunction "2_2") (pintype "passive"))
      (node (ref "SENSOR") (pin "F2") (pinfunction "CMDP_F2") (pintype "bidirectional"))
    )
    (net (code "111") (name "Net-(SENSORB-CMDP_COMP)") (class "Default")
      (node (ref "C28") (pin "2") (pinfunction "2_2") (pintype "passive"))
      (node (ref "SENSOR") (pin "H3") (pinfunction "CMDP_COMP_H3") (pintype "bidirectional"))
    )
    (net (code "112") (name "Net-(SENSORB-CMDP_COMP_INV)") (class "Default")
      (node (ref "C27") (pin "2") (pinfunction "2_2") (pintype "passive"))
      (node (ref "SENSOR") (pin "F3") (pinfunction "CMDP_COMP_INV_F3") (pintype "bidirectional"))
    )
    (net (code "113") (name "Net-(SENSORB-CMD_COLAMP)") (class "Default")
      (node (ref "C25") (pin "2") (pinfunction "2_2") (pintype "passive"))
      (node (ref "SENSOR") (pin "C6") (pinfunction "CMD_COLAMP_C6") (pintype "bidirectional"))
    )
    (net (code "114") (name "Net-(SENSORB-CMD_COL_LOAD)") (class "Default")
      (node (ref "C23") (pin "2") (pinfunction "2_2") (pintype "passive"))
      (node (ref "SENSOR") (pin "B1") (pinfunction "CMD_COL_LOAD_B1") (pintype "bidirectional"))
    )
    (net (code "115") (name "Net-(SENSORB-CMD_COL_PC)") (class "Default")
      (node (ref "C26") (pin "2") (pinfunction "2_2") (pintype "passive"))
      (node (ref "SENSOR") (pin "D1") (pinfunction "CMD_COL_PC_D1") (pintype "bidirectional"))
    )
    (net (code "116") (name "Net-(SENSORB-CMD_LVDS)") (class "Default")
      (node (ref "C62") (pin "1") (pinfunction "1_1") (pintype "passive"))
      (node (ref "SENSOR") (pin "C1") (pinfunction "CMD_LVDS_C1") (pintype "bidirectional"))
    )
    (net (code "117") (name "Net-(SENSORB-CMD_RAMP)") (class "Default")
      (node (ref "C24") (pin "2") (pinfunction "2_2") (pintype "passive"))
      (node (ref "SENSOR") (pin "B29") (pinfunction "CMD_RAMP_B29") (pintype "bidirectional"))
    )
    (net (code "118") (name "Net-(SENSORB-VBGAP)") (class "Default")
      (node (ref "C64") (pin "1") (pinfunction "1_1") (pintype "passive"))
      (node (ref "SENSOR") (pin "C29") (pinfunction "VBGAP_C29") (pintype "bidirectional"))
    )
    (net (code "119") (name "Net-(SENSORB-VCLAMP)") (class "Default")
      (node (ref "C63") (pin "1") (pinfunction "1_1") (pintype "passive"))
      (node (ref "SENSOR") (pin "D4") (pinfunction "VCLAMP_D4") (pintype "bidirectional"))
    )
    (net (code "120") (name "Net-(SENSORB-VCLAMP_ADC)") (class "Default")
      (node (ref "C60") (pin "1") (pinfunction "1_1") (pintype "passive"))
      (node (ref "SENSOR") (pin "G2") (pinfunction "VCLAMP_ADC_G2") (pintype "bidirectional"))
    )
    (net (code "121") (name "Net-(SENSORB-VPCH_H)") (class "Default")
      (node (ref "C71") (pin "1") (pinfunction "1_1") (pintype "passive"))
      (node (ref "SENSOR") (pin "C4") (pinfunction "VPCH_H_C4") (pintype "bidirectional"))
    )
    (net (code "122") (name "Net-(SENSORB-VPCH_L)") (class "Default")
      (node (ref "C14") (pin "1") (pinfunction "1_1") (pintype "passive"))
      (node (ref "SENSOR") (pin "A4") (pinfunction "VPCH_L_A4") (pintype "bidirectional"))
    )
    (net (code "123") (name "Net-(SENSORB-VREF)") (class "Default")
      (node (ref "C29") (pin "1") (pinfunction "1_1") (pintype "passive"))
      (node (ref "SENSOR") (pin "A3") (pinfunction "VREF_A3") (pintype "bidirectional"))
    )
    (net (code "124") (name "Net-(SENSORB-VREF_ADC)") (class "Default")
      (node (ref "C30") (pin "1") (pinfunction "1_1") (pintype "passive"))
      (node (ref "SENSOR") (pin "B3") (pinfunction "VREF_ADC_B3") (pintype "bidirectional"))
    )
    (net (code "125") (name "Net-(SENSORB-VRES_L)") (class "Default")
      (node (ref "C15") (pin "1") (pinfunction "1_1") (pintype "passive"))
      (node (ref "SENSOR") (pin "D5") (pinfunction "VRES_L_D5") (pintype "bidirectional"))
    )
    (net (code "126") (name "Net-(SENSORB-VTF_LOW0)") (class "Default")
      (node (ref "C18") (pin "1") (pinfunction "1_1") (pintype "passive"))
      (node (ref "SENSOR") (pin "C5") (pinfunction "VTF_LOW0_C5") (pintype "bidirectional"))
    )
    (net (code "127") (name "Net-(SENSORB-VTF_LOW1)") (class "Default")
      (node (ref "C19") (pin "1") (pinfunction "1_1") (pintype "passive"))
      (node (ref "SENSOR") (pin "D6") (pinfunction "VTF_LOW1_D6") (pintype "bidirectional"))
    )
    (net (code "128") (name "Net-(SENSORB-VTF_LOW2)") (class "Default")
      (node (ref "C20") (pin "1") (pinfunction "1_1") (pintype "passive"))
      (node (ref "SENSOR") (pin "B30") (pinfunction "VTF_LOW2_B30") (pintype "bidirectional"))
    )
    (net (code "129") (name "Net-(SENSORB-VTF_LOW3)") (class "Default")
      (node (ref "C21") (pin "1") (pinfunction "1_1") (pintype "passive"))
      (node (ref "SENSOR") (pin "C30") (pinfunction "VTF_LOW3_C30") (pintype "bidirectional"))
    )
    (net (code "130") (name "Net-(U3-ADJ)") (class "Default")
      (node (ref "R21") (pin "1") (pinfunction "1_1") (pintype "passive"))
      (node (ref "R22") (pin "2") (pinfunction "2_2") (pintype "passive"))
      (node (ref "U3") (pin "5") (pinfunction "ADJ_5") (pintype "input"))
    )
    (net (code "131") (name "Net-(U6-B4)") (class "Default")
      (node (ref "TP9") (pin "TP") (pinfunction "TP_TP") (pintype "input"))
      (node (ref "U6") (pin "9") (pinfunction "B4_9") (pintype "bidirectional"))
    )
    (net (code "132") (name "Net-(UEP-WP)") (class "Default")
      (node (ref "R1X") (pin "2") (pinfunction "2_2") (pintype "passive"))
      (node (ref "R2X") (pin "1") (pinfunction "1_1") (pintype "passive"))
      (node (ref "UEP") (pin "7") (pinfunction "WP_7") (pintype "input"))
    )
    (net (code "133") (name "Net-(UNE-VINA+)") (class "Default")
      (node (ref "R7") (pin "2") (pinfunction "2_2") (pintype "passive"))
      (node (ref "R8") (pin "1") (pinfunction "1_1") (pintype "passive"))
      (node (ref "UNE") (pin "3") (pinfunction "VINA+_3") (pintype "input"))
    )
    (net (code "134") (name "Net-(UNE-VINB-)") (class "Default")
      (node (ref "R8") (pin "2") (pinfunction "2_2") (pintype "passive"))
      (node (ref "R9") (pin "1") (pinfunction "1_1") (pintype "passive"))
      (node (ref "UNE") (pin "6") (pinfunction "VINB-_6") (pintype "input"))
    )
    (net (code "135") (name "Net-(UNN-VINA+)") (class "Default")
      (node (ref "R4") (pin "2") (pinfunction "2_2") (pintype "passive"))
      (node (ref "R5") (pin "1") (pinfunction "1_1") (pintype "passive"))
      (node (ref "UNN") (pin "3") (pinfunction "VINA+_3") (pintype "input"))
    )
    (net (code "136") (name "Net-(UNN-VINB-)") (class "Default")
      (node (ref "R5") (pin "2") (pinfunction "2_2") (pintype "passive"))
      (node (ref "R6") (pin "1") (pinfunction "1_1") (pintype "passive"))
      (node (ref "UNN") (pin "6") (pinfunction "VINB-_6") (pintype "input"))
    )
    (net (code "137") (name "Net-(UNW-VINA+)") (class "Default")
      (node (ref "R1") (pin "2") (pinfunction "2_2") (pintype "passive"))
      (node (ref "R2") (pin "1") (pinfunction "1_1") (pintype "passive"))
      (node (ref "UNW") (pin "3") (pinfunction "VINA+_3") (pintype "input"))
    )
    (net (code "138") (name "Net-(UNW-VINB-)") (class "Default")
      (node (ref "R2") (pin "2") (pinfunction "2_2") (pintype "passive"))
      (node (ref "R3") (pin "1") (pinfunction "1_1") (pintype "passive"))
      (node (ref "UNW") (pin "6") (pinfunction "VINB-_6") (pintype "input"))
    )
    (net (code "139") (name "Net-(USE-VINA+)") (class "Default")
      (node (ref "R10") (pin "2") (pinfunction "2_2") (pintype "passive"))
      (node (ref "R11") (pin "1") (pinfunction "1_1") (pintype "passive"))
      (node (ref "USE") (pin "3") (pinfunction "VINA+_3") (pintype "input"))
    )
    (net (code "140") (name "Net-(USE-VINB-)") (class "Default")
      (node (ref "R11") (pin "2") (pinfunction "2_2") (pintype "passive"))
      (node (ref "R12") (pin "1") (pinfunction "1_1") (pintype "passive"))
      (node (ref "USE") (pin "6") (pinfunction "VINB-_6") (pintype "input"))
    )
    (net (code "141") (name "Net-(USS-VINA+)") (class "Default")
      (node (ref "R13") (pin "2") (pinfunction "2_2") (pintype "passive"))
      (node (ref "R14") (pin "1") (pinfunction "1_1") (pintype "passive"))
      (node (ref "USS") (pin "3") (pinfunction "VINA+_3") (pintype "input"))
    )
    (net (code "142") (name "Net-(USS-VINB-)") (class "Default")
      (node (ref "R14") (pin "2") (pinfunction "2_2") (pintype "passive"))
      (node (ref "R15") (pin "1") (pinfunction "1_1") (pintype "passive"))
      (node (ref "USS") (pin "6") (pinfunction "VINB-_6") (pintype "input"))
    )
    (net (code "143") (name "Net-(USW-VINA+)") (class "Default")
      (node (ref "R16") (pin "2") (pinfunction "2_2") (pintype "passive"))
      (node (ref "R17") (pin "1") (pinfunction "1_1") (pintype "passive"))
      (node (ref "USW") (pin "3") (pinfunction "VINA+_3") (pintype "input"))
    )
    (net (code "144") (name "Net-(USW-VINB-)") (class "Default")
      (node (ref "R17") (pin "2") (pinfunction "2_2") (pintype "passive"))
      (node (ref "R18") (pin "1") (pinfunction "1_1") (pintype "passive"))
      (node (ref "USW") (pin "6") (pinfunction "VINB-_6") (pintype "input"))
    )
    (net (code "145") (name "S00_N") (class "Default")
      (node (ref "X-SOUTH") (pin "16") (pinfunction "16_16") (pintype "bidirectional"))
    )
    (net (code "146") (name "S00_P") (class "Default")
      (node (ref "X-SOUTH") (pin "14") (pinfunction "14_14") (pintype "bidirectional"))
    )
    (net (code "147") (name "S01_N") (class "Default")
      (node (ref "X-SOUTH") (pin "17") (pinfunction "17_17") (pintype "bidirectional"))
    )
    (net (code "148") (name "S01_P") (class "Default")
      (node (ref "X-SOUTH") (pin "15") (pinfunction "15_15") (pintype "bidirectional"))
    )
    (net (code "149") (name "S02_N") (class "Default")
      (node (ref "X-SOUTH") (pin "22") (pinfunction "22_22") (pintype "bidirectional"))
    )
    (net (code "150") (name "S02_P") (class "Default")
      (node (ref "X-SOUTH") (pin "20") (pinfunction "20_20") (pintype "bidirectional"))
    )
    (net (code "151") (name "S03_N") (class "Default")
      (node (ref "X-SOUTH") (pin "23") (pinfunction "23_23") (pintype "bidirectional"))
    )
    (net (code "152") (name "S03_P") (class "Default")
      (node (ref "X-SOUTH") (pin "21") (pinfunction "21_21") (pintype "bidirectional"))
    )
    (net (code "153") (name "S04_N") (class "Default")
      (node (ref "SENSOR") (pin "C24") (pinfunction "OUT32_N_C24") (pintype "output"))
      (node (ref "X-SOUTH") (pin "28") (pinfunction "28_28") (pintype "bidirectional"))
    )
    (net (code "154") (name "S04_P") (class "Default")
      (node (ref "SENSOR") (pin "C25") (pinfunction "OUT32_P_C25") (pintype "output"))
      (node (ref "X-SOUTH") (pin "26") (pinfunction "26_26") (pintype "bidirectional"))
    )
    (net (code "155") (name "S05_N") (class "Default")
      (node (ref "X-SOUTH") (pin "29") (pinfunction "29_29") (pintype "bidirectional"))
    )
    (net (code "156") (name "S05_P") (class "Default")
      (node (ref "X-SOUTH") (pin "27") (pinfunction "27_27") (pintype "bidirectional"))
    )
    (net (code "157") (name "S06_N") (class "Default")
      (node (ref "SENSOR") (pin "D23") (pinfunction "OUT30_N_D23") (pintype "output"))
      (node (ref "X-SOUTH") (pin "34") (pinfunction "34_34") (pintype "bidirectional"))
    )
    (net (code "158") (name "S06_P") (class "Default")
      (node (ref "SENSOR") (pin "D24") (pinfunction "OUT30_P_D24") (pintype "output"))
      (node (ref "X-SOUTH") (pin "32") (pinfunction "32_32") (pintype "bidirectional"))
    )
    (net (code "159") (name "S07_N") (class "Default")
      (node (ref "SENSOR") (pin "B24") (pinfunction "OUT31_N_B24") (pintype "output"))
      (node (ref "X-SOUTH") (pin "35") (pinfunction "35_35") (pintype "bidirectional"))
    )
    (net (code "160") (name "S07_P") (class "Default")
      (node (ref "SENSOR") (pin "B25") (pinfunction "OUT31_P_B25") (pintype "output"))
      (node (ref "X-SOUTH") (pin "33") (pinfunction "33_33") (pintype "bidirectional"))
    )
    (net (code "161") (name "S08_N") (class "Default")
      (node (ref "SENSOR") (pin "D21") (pinfunction "OUT27_N_D21") (pintype "output"))
      (node (ref "X-SOUTH") (pin "40") (pinfunction "40_40") (pintype "bidirectional"))
    )
    (net (code "162") (name "S08_P") (class "Default")
      (node (ref "SENSOR") (pin "D22") (pinfunction "OUT27_P_D22") (pintype "output"))
      (node (ref "X-SOUTH") (pin "38") (pinfunction "38_38") (pintype "bidirectional"))
    )
    (net (code "163") (name "S09_N") (class "Default")
      (node (ref "SENSOR") (pin "A23") (pinfunction "OUT29_N_A23") (pintype "output"))
      (node (ref "X-SOUTH") (pin "41") (pinfunction "41_41") (pintype "bidirectional"))
    )
    (net (code "164") (name "S09_P") (class "Default")
      (node (ref "SENSOR") (pin "A24") (pinfunction "OUT29_P_A24") (pintype "output"))
      (node (ref "X-SOUTH") (pin "39") (pinfunction "39_39") (pintype "bidirectional"))
    )
    (net (code "165") (name "S10_N") (class "Default")
      (node (ref "SENSOR") (pin "C21") (pinfunction "OUT28_N_C21") (pintype "output"))
      (node (ref "X-SOUTH") (pin "46") (pinfunction "46_46") (pintype "bidirectional"))
    )
    (net (code "166") (name "S10_P") (class "Default")
      (node (ref "SENSOR") (pin "C22") (pinfunction "OUT28_P_C22") (pintype "output"))
      (node (ref "X-SOUTH") (pin "44") (pinfunction "44_44") (pintype "bidirectional"))
    )
    (net (code "167") (name "S11_N") (class "Default")
      (node (ref "SENSOR") (pin "B20") (pinfunction "OUT26_N_B20") (pintype "output"))
      (node (ref "X-SOUTH") (pin "47") (pinfunction "47_47") (pintype "bidirectional"))
    )
    (net (code "168") (name "S11_P") (class "Default")
      (node (ref "SENSOR") (pin "B21") (pinfunction "OUT26_P_B21") (pintype "output"))
      (node (ref "X-SOUTH") (pin "45") (pinfunction "45_45") (pintype "bidirectional"))
    )
    (net (code "169") (name "S12_N") (class "Default")
      (node (ref "SENSOR") (pin "D19") (pinfunction "OUT24_N_D19") (pintype "output"))
      (node (ref "X-SOUTH") (pin "52") (pinfunction "52_52") (pintype "bidirectional"))
    )
    (net (code "170") (name "S12_P") (class "Default")
      (node (ref "SENSOR") (pin "D20") (pinfunction "OUT24_P_D20") (pintype "output"))
      (node (ref "X-SOUTH") (pin "50") (pinfunction "50_50") (pintype "bidirectional"))
    )
    (net (code "171") (name "S13_N") (class "Default")
      (node (ref "SENSOR") (pin "A19") (pinfunction "OUT23_N_A19") (pintype "output"))
      (node (ref "X-SOUTH") (pin "53") (pinfunction "53_53") (pintype "bidirectional"))
    )
    (net (code "172") (name "S13_P") (class "Default")
      (node (ref "SENSOR") (pin "A20") (pinfunction "OUT23_P_A20") (pintype "output"))
      (node (ref "X-SOUTH") (pin "51") (pinfunction "51_51") (pintype "bidirectional"))
    )
    (net (code "173") (name "S14_N") (class "Default")
      (node (ref "SENSOR") (pin "C19") (pinfunction "OUT25_N_C19") (pintype "output"))
      (node (ref "X-SOUTH") (pin "58") (pinfunction "58_58") (pintype "bidirectional"))
    )
    (net (code "174") (name "S14_P") (class "Default")
      (node (ref "SENSOR") (pin "C20") (pinfunction "OUT25_P_C20") (pintype "output"))
      (node (ref "X-SOUTH") (pin "56") (pinfunction "56_56") (pintype "bidirectional"))
    )
    (net (code "175") (name "S15_N") (class "Default")
      (node (ref "SENSOR") (pin "B18") (pinfunction "OUT22_N_B18") (pintype "output"))
      (node (ref "X-SOUTH") (pin "59") (pinfunction "59_59") (pintype "bidirectional"))
    )
    (net (code "176") (name "S15_P") (class "Default")
      (node (ref "SENSOR") (pin "B19") (pinfunction "OUT22_P_B19") (pintype "output"))
      (node (ref "X-SOUTH") (pin "57") (pinfunction "57_57") (pintype "bidirectional"))
    )
    (net (code "177") (name "S16_N") (class "Default")
      (node (ref "SENSOR") (pin "C17") (pinfunction "OUT21_N_C17") (pintype "output"))
      (node (ref "X-SOUTH") (pin "64") (pinfunction "64_64") (pintype "bidirectional"))
    )
    (net (code "178") (name "S16_P") (class "Default")
      (node (ref "SENSOR") (pin "C18") (pinfunction "OUT21_P_C18") (pintype "output"))
      (node (ref "X-SOUTH") (pin "62") (pinfunction "62_62") (pintype "bidirectional"))
    )
    (net (code "179") (name "S17_N") (class "Default")
      (node (ref "SENSOR") (pin "A17") (pinfunction "OUT19_N_A17") (pintype "output"))
      (node (ref "X-SOUTH") (pin "65") (pinfunction "65_65") (pintype "bidirectional"))
    )
    (net (code "180") (name "S17_P") (class "Default")
      (node (ref "SENSOR") (pin "A18") (pinfunction "OUT19_P_A18") (pintype "output"))
      (node (ref "X-SOUTH") (pin "63") (pinfunction "63_63") (pintype "bidirectional"))
    )
    (net (code "181") (name "S18_N") (class "Default")
      (node (ref "SENSOR") (pin "D17") (pinfunction "OUT20_N_D17") (pintype "output"))
      (node (ref "X-SOUTH") (pin "70") (pinfunction "70_70") (pintype "bidirectional"))
    )
    (net (code "182") (name "S18_P") (class "Default")
      (node (ref "SENSOR") (pin "D18") (pinfunction "OUT20_P_D18") (pintype "output"))
      (node (ref "X-SOUTH") (pin "68") (pinfunction "68_68") (pintype "bidirectional"))
    )
    (net (code "183") (name "S19_N") (class "Default")
      (node (ref "SENSOR") (pin "B16") (pinfunction "OUT18_N_B16") (pintype "output"))
      (node (ref "X-SOUTH") (pin "71") (pinfunction "71_71") (pintype "bidirectional"))
    )
    (net (code "184") (name "S19_P") (class "Default")
      (node (ref "SENSOR") (pin "B17") (pinfunction "OUT18_P_B17") (pintype "output"))
      (node (ref "X-SOUTH") (pin "69") (pinfunction "69_69") (pintype "bidirectional"))
    )
    (net (code "185") (name "S20_N") (class "Default")
      (node (ref "SENSOR") (pin "D15") (pinfunction "OUT17_N_D15") (pintype "output"))
      (node (ref "X-SOUTH") (pin "76") (pinfunction "76_76") (pintype "bidirectional"))
    )
    (net (code "186") (name "S20_P") (class "Default")
      (node (ref "SENSOR") (pin "D16") (pinfunction "OUT17_P_D16") (pintype "output"))
      (node (ref "X-SOUTH") (pin "74") (pinfunction "74_74") (pintype "bidirectional"))
    )
    (net (code "187") (name "S21_N") (class "Default")
      (node (ref "SENSOR") (pin "B14") (pinfunction "OUT16_N_B14") (pintype "output"))
      (node (ref "X-SOUTH") (pin "77") (pinfunction "77_77") (pintype "bidirectional"))
    )
    (net (code "188") (name "S21_P") (class "Default")
      (node (ref "SENSOR") (pin "B15") (pinfunction "OUT16_P_B15") (pintype "output"))
      (node (ref "X-SOUTH") (pin "75") (pinfunction "75_75") (pintype "bidirectional"))
    )
    (net (code "189") (name "S22_N") (class "Default")
      (node (ref "SENSOR") (pin "D13") (pinfunction "OUT15_N_D13") (pintype "output"))
      (node (ref "X-SOUTH") (pin "82") (pinfunction "82_82") (pintype "bidirectional"))
    )
    (net (code "190") (name "S22_P") (class "Default")
      (node (ref "SENSOR") (pin "D14") (pinfunction "OUT15_P_D14") (pintype "output"))
      (node (ref "X-SOUTH") (pin "80") (pinfunction "80_80") (pintype "bidirectional"))
    )
    (net (code "191") (name "S23_N") (class "Default")
      (node (ref "SENSOR") (pin "A13") (pinfunction "OUT13_N_A13") (pintype "output"))
      (node (ref "X-SOUTH") (pin "83") (pinfunction "83_83") (pintype "bidirectional"))
    )
    (net (code "192") (name "S23_P") (class "Default")
      (node (ref "SENSOR") (pin "A14") (pinfunction "OUT13_P_A14") (pintype "output"))
      (node (ref "X-SOUTH") (pin "81") (pinfunction "81_81") (pintype "bidirectional"))
    )
    (net (code "193") (name "S24_N") (class "Default")
      (node (ref "SENSOR") (pin "C13") (pinfunction "OUT14_N_C13") (pintype "output"))
      (node (ref "X-SOUTH") (pin "88") (pinfunction "88_88") (pintype "bidirectional"))
    )
    (net (code "194") (name "S24_P") (class "Default")
      (node (ref "SENSOR") (pin "C14") (pinfunction "OUT14_P_C14") (pintype "output"))
      (node (ref "X-SOUTH") (pin "86") (pinfunction "86_86") (pintype "bidirectional"))
    )
    (net (code "195") (name "S25_N") (class "Default")
      (node (ref "SENSOR") (pin "B12") (pinfunction "OUT12_N_B12") (pintype "output"))
      (node (ref "X-SOUTH") (pin "89") (pinfunction "89_89") (pintype "bidirectional"))
    )
    (net (code "196") (name "S25_P") (class "Default")
      (node (ref "SENSOR") (pin "B13") (pinfunction "OUT12_P_B13") (pintype "output"))
      (node (ref "X-SOUTH") (pin "87") (pinfunction "87_87") (pintype "bidirectional"))
    )
    (net (code "197") (name "S26_N") (class "Default")
      (node (ref "SENSOR") (pin "D11") (pinfunction "OUT10_N_D11") (pintype "output"))
      (node (ref "X-SOUTH") (pin "94") (pinfunction "94_94") (pintype "bidirectional"))
    )
    (net (code "198") (name "S26_P") (class "Default")
      (node (ref "SENSOR") (pin "D12") (pinfunction "OUT10_P_D12") (pintype "output"))
      (node (ref "X-SOUTH") (pin "92") (pinfunction "92_92") (pintype "bidirectional"))
    )
    (net (code "199") (name "S27_N") (class "Default")
      (node (ref "SENSOR") (pin "A11") (pinfunction "OUT9_N_A11") (pintype "output"))
      (node (ref "X-SOUTH") (pin "95") (pinfunction "95_95") (pintype "bidirectional"))
    )
    (net (code "200") (name "S27_P") (class "Default")
      (node (ref "SENSOR") (pin "A12") (pinfunction "OUT9_P_A12") (pintype "output"))
      (node (ref "X-SOUTH") (pin "93") (pinfunction "93_93") (pintype "bidirectional"))
    )
    (net (code "201") (name "S28_N") (class "Default")
      (node (ref "SENSOR") (pin "C11") (pinfunction "OUT11_N_C11") (pintype "output"))
      (node (ref "X-SOUTH") (pin "100") (pinfunction "100_100") (pintype "bidirectional"))
    )
    (net (code "202") (name "S28_P") (class "Default")
      (node (ref "SENSOR") (pin "C12") (pinfunction "OUT11_P_C12") (pintype "output"))
      (node (ref "X-SOUTH") (pin "98") (pinfunction "98_98") (pintype "bidirectional"))
    )
    (net (code "203") (name "S29_N") (class "Default")
      (node (ref "SENSOR") (pin "B10") (pinfunction "OUT8_N_B10") (pintype "output"))
      (node (ref "X-SOUTH") (pin "101") (pinfunction "101_101") (pintype "bidirectional"))
    )
    (net (code "204") (name "S29_P") (class "Default")
      (node (ref "SENSOR") (pin "B11") (pinfunction "OUT8_P_B11") (pintype "output"))
      (node (ref "X-SOUTH") (pin "99") (pinfunction "99_99") (pintype "bidirectional"))
    )
    (net (code "205") (name "S30_N") (class "Default")
      (node (ref "SENSOR") (pin "C9") (pinfunction "OUT7_N_C9") (pintype "output"))
      (node (ref "X-SOUTH") (pin "106") (pinfunction "106_106") (pintype "bidirectional"))
    )
    (net (code "206") (name "S30_P") (class "Default")
      (node (ref "SENSOR") (pin "C10") (pinfunction "OUT7_P_C10") (pintype "output"))
      (node (ref "X-SOUTH") (pin "104") (pinfunction "104_104") (pintype "bidirectional"))
    )
    (net (code "207") (name "S31_N") (class "Default")
      (node (ref "SENSOR") (pin "B8") (pinfunction "OUT5_N_B8") (pintype "output"))
      (node (ref "X-SOUTH") (pin "107") (pinfunction "107_107") (pintype "bidirectional"))
    )
    (net (code "208") (name "S31_P") (class "Default")
      (node (ref "SENSOR") (pin "B9") (pinfunction "OUT5_P_B9") (pintype "output"))
      (node (ref "X-SOUTH") (pin "105") (pinfunction "105_105") (pintype "bidirectional"))
    )
    (net (code "209") (name "S32_N") (class "Default")
      (node (ref "SENSOR") (pin "D9") (pinfunction "OUT6_N_D9") (pintype "output"))
      (node (ref "X-SOUTH") (pin "112") (pinfunction "112_112") (pintype "bidirectional"))
    )
    (net (code "210") (name "S32_P") (class "Default")
      (node (ref "SENSOR") (pin "D10") (pinfunction "OUT6_P_D10") (pintype "output"))
      (node (ref "X-SOUTH") (pin "110") (pinfunction "110_110") (pintype "bidirectional"))
    )
    (net (code "211") (name "S33_N") (class "Default")
      (node (ref "SENSOR") (pin "A7") (pinfunction "OUT2_N_A7") (pintype "output"))
      (node (ref "X-SOUTH") (pin "113") (pinfunction "113_113") (pintype "bidirectional"))
    )
    (net (code "212") (name "S33_P") (class "Default")
      (node (ref "SENSOR") (pin "A8") (pinfunction "OUT2_P_A8") (pintype "output"))
      (node (ref "X-SOUTH") (pin "111") (pinfunction "111_111") (pintype "bidirectional"))
    )
    (net (code "213") (name "S34_N") (class "Default")
      (node (ref "SENSOR") (pin "C7") (pinfunction "OUT4_N_C7") (pintype "output"))
      (node (ref "X-SOUTH") (pin "118") (pinfunction "118_118") (pintype "bidirectional"))
    )
    (net (code "214") (name "S34_P") (class "Default")
      (node (ref "SENSOR") (pin "C8") (pinfunction "OUT4_P_C8") (pintype "output"))
      (node (ref "X-SOUTH") (pin "116") (pinfunction "116_116") (pintype "bidirectional"))
    )
    (net (code "215") (name "S35_N") (class "Default")
      (node (ref "SENSOR") (pin "B6") (pinfunction "OUT1_N_B6") (pintype "output"))
      (node (ref "X-SOUTH") (pin "119") (pinfunction "119_119") (pintype "bidirectional"))
    )
    (net (code "216") (name "S35_P") (class "Default")
      (node (ref "SENSOR") (pin "B7") (pinfunction "OUT1_P_B7") (pintype "output"))
      (node (ref "X-SOUTH") (pin "117") (pinfunction "117_117") (pintype "bidirectional"))
    )
    (net (code "217") (name "S36_N") (class "Default")
      (node (ref "SENSOR") (pin "D7") (pinfunction "OUT3_N_D7") (pintype "output"))
      (node (ref "X-SOUTH") (pin "124") (pinfunction "124_124") (pintype "bidirectional"))
    )
    (net (code "218") (name "S36_P") (class "Default")
      (node (ref "SENSOR") (pin "D8") (pinfunction "OUT3_P_D8") (pintype "output"))
      (node (ref "X-SOUTH") (pin "122") (pinfunction "122_122") (pintype "bidirectional"))
    )
    (net (code "219") (name "S37_N") (class "Default")
      (node (ref "SENSOR") (pin "A5") (pinfunction "OUTCTR_N_A5") (pintype "output"))
      (node (ref "X-SOUTH") (pin "125") (pinfunction "125_125") (pintype "bidirectional"))
    )
    (net (code "220") (name "S37_P") (class "Default")
      (node (ref "SENSOR") (pin "A6") (pinfunction "OUTCTR_P_A6") (pintype "output"))
      (node (ref "X-SOUTH") (pin "123") (pinfunction "123_123") (pintype "bidirectional"))
    )
    (net (code "221") (name "S38_N") (class "Default")
      (node (ref "X-SOUTH") (pin "130") (pinfunction "130_130") (pintype "bidirectional"))
    )
    (net (code "222") (name "S38_P") (class "Default")
      (node (ref "X-SOUTH") (pin "128") (pinfunction "128_128") (pintype "bidirectional"))
    )
    (net (code "223") (name "S39_N") (class "Default")
      (node (ref "U3") (pin "6") (pinfunction "EN_6") (pintype "input"))
      (node (ref "X-SOUTH") (pin "131") (pinfunction "131_131") (pintype "bidirectional"))
    )
    (net (code "224") (name "S39_P") (class "Default")
      (node (ref "X-SOUTH") (pin "129") (pinfunction "129_129") (pintype "bidirectional"))
    )
    (net (code "225") (name "SPI_CLK") (class "Default")
      (node (ref "SENSOR") (pin "H29") (pinfunction "SPI_CLK_H29") (pintype "input"))
      (node (ref "U4") (pin "9") (pinfunction "B4_9") (pintype "bidirectional"))
    )
    (net (code "226") (name "SPI_EN") (class "Default")
      (node (ref "SENSOR") (pin "F28") (pinfunction "SPI_EN_F28") (pintype "input"))
      (node (ref "U4") (pin "12") (pinfunction "B1_12") (pintype "bidirectional"))
    )
    (net (code "227") (name "SPI_IN") (class "Default")
      (node (ref "SENSOR") (pin "E28") (pinfunction "SPI_IN_E28") (pintype "input"))
      (node (ref "U4") (pin "10") (pinfunction "B3_10") (pintype "bidirectional"))
    )
    (net (code "228") (name "SPI_OUT") (class "Default")
      (node (ref "SENSOR") (pin "G28") (pinfunction "SPI_OUT_G28") (pintype "output"))
      (node (ref "U4") (pin "11") (pinfunction "B2_11") (pintype "bidirectional"))
    )
    (net (code "229") (name "SYS_RES_N") (class "Default")
      (node (ref "SENSOR") (pin "F30") (pinfunction "SYS_RES_N_F30") (pintype "input"))
      (node (ref "U5") (pin "10") (pinfunction "B3_10") (pintype "bidirectional"))
    )
    (net (code "230") (name "S_CHK_EN") (class "Default")
      (node (ref "X-SOUTH") (pin "8") (pinfunction "8_8") (pintype "bidirectional"))
    )
    (net (code "231") (name "S_CHK_V") (class "Default")
      (node (ref "C5") (pin "1") (pinfunction "1_1") (pintype "passive"))
      (node (ref "C6") (pin "1") (pinfunction "1_1") (pintype "passive"))
      (node (ref "C7") (pin "1") (pinfunction "1_1") (pintype "passive"))
      (node (ref "R20") (pin "1") (pinfunction "1_1") (pintype "passive"))
      (node (ref "TP3") (pin "TP") (pinfunction "TP_TP") (pintype "input"))
      (node (ref "USE") (pin "8") (pinfunction "VDD_8") (pintype "power_in"))
      (node (ref "USS") (pin "8") (pinfunction "VDD_8") (pintype "power_in"))
      (node (ref "USW") (pin "8") (pinfunction "VDD_8") (pintype "power_in"))
      (node (ref "X-SOUTH") (pin "10") (pinfunction "10_10") (pintype "bidirectional"))
    )
    (net (code "232") (name "S_I2C_EN") (class "Default")
      (node (ref "X-SOUTH") (pin "137") (pinfunction "137_137") (pintype "bidirectional"))
    )
    (net (code "233") (name "S_I2C_V") (class "Default")
      (node (ref "U7") (pin "8") (pinfunction "VCC_8") (pintype "power_in"))
      (node (ref "X-SOUTH") (pin "135") (pinfunction "135_135") (pintype "bidirectional"))
    )
    (net (code "234") (name "S_REF") (class "Default")
      (node (ref "R20") (pin "2") (pinfunction "2_2") (pintype "passive"))
      (node (ref "TP4") (pin "TP") (pinfunction "TP_TP") (pintype "input"))
      (node (ref "U2") (pin "1") (pinfunction "CATHODE_1") (pintype "output"))
      (node (ref "U2") (pin "3") (pinfunction "REF_3") (pintype "input"))
      (node (ref "USE") (pin "2") (pinfunction "VINA-_2") (pintype "input"))
      (node (ref "USE") (pin "5") (pinfunction "VINB+_5") (pintype "input"))
      (node (ref "USS") (pin "2") (pinfunction "VINA-_2") (pintype "input"))
      (node (ref "USS") (pin "5") (pinfunction "VINB+_5") (pintype "input"))
      (node (ref "USW") (pin "2") (pinfunction "VINA-_2") (pintype "input"))
      (node (ref "USW") (pin "5") (pinfunction "VINB+_5") (pintype "input"))
    )
    (net (code "235") (name "S_SCK") (class "Default")
      (node (ref "X-SOUTH") (pin "144") (pinfunction "144_144") (pintype "bidirectional"))
    )
    (net (code "236") (name "S_SCL") (class "Default")
      (node (ref "U7") (pin "2") (pinfunction "SCL_2") (pintype "input"))
      (node (ref "X-SOUTH") (pin "143") (pinfunction "143_143") (pintype "bidirectional"))
    )
    (net (code "237") (name "S_SDA") (class "Default")
      (node (ref "U7") (pin "1") (pinfunction "SDA_1") (pintype "bidirectional"))
      (node (ref "X-SOUTH") (pin "141") (pinfunction "141_141") (pintype "bidirectional"))
    )
    (net (code "238") (name "S_SDI") (class "Default")
      (node (ref "X-SOUTH") (pin "140") (pinfunction "140_140") (pintype "bidirectional"))
    )
    (net (code "239") (name "S_SDO") (class "Default")
      (node (ref "X-SOUTH") (pin "142") (pinfunction "142_142") (pintype "bidirectional"))
    )
    (net (code "240") (name "S_SPI_EN") (class "Default")
      (node (ref "X-SOUTH") (pin "136") (pinfunction "136_136") (pintype "bidirectional"))
    )
    (net (code "241") (name "S_SPI_V") (class "Default")
      (node (ref "X-SOUTH") (pin "134") (pinfunction "134_134") (pintype "bidirectional"))
    )
    (net (code "242") (name "S_VE") (class "Default")
      (node (ref "X-SOUTH") (pin "13") (pinfunction "13_13") (pintype "bidirectional"))
      (node (ref "X-SOUTH") (pin "19") (pinfunction "19_19") (pintype "bidirectional"))
      (node (ref "X-SOUTH") (pin "25") (pinfunction "25_25") (pintype "bidirectional"))
      (node (ref "X-SOUTH") (pin "31") (pinfunction "31_31") (pintype "bidirectional"))
      (node (ref "X-SOUTH") (pin "37") (pinfunction "37_37") (pintype "bidirectional"))
    )
    (net (code "243") (name "S_VE_CV") (class "Default")
      (node (ref "C11") (pin "1") (pinfunction "1_1") (pintype "passive"))
      (node (ref "R10") (pin "1") (pinfunction "1_1") (pintype "passive"))
      (node (ref "X-SOUTH") (pin "2") (pinfunction "2_2") (pintype "bidirectional"))
    )
    (net (code "244") (name "S_VE_OV") (class "Default")
      (node (ref "USE") (pin "7") (pinfunction "OUTB_7") (pintype "output"))
      (node (ref "X-SOUTH") (pin "1") (pinfunction "1_1") (pintype "bidirectional"))
    )
    (net (code "245") (name "S_VE_UV") (class "Default")
      (node (ref "USE") (pin "1") (pinfunction "OUTA_1") (pintype "output"))
      (node (ref "X-SOUTH") (pin "7") (pinfunction "7_7") (pintype "bidirectional"))
    )
    (net (code "246") (name "S_VS") (class "Default")
      (node (ref "C45") (pin "1") (pinfunction "1_1") (pintype "passive"))
      (node (ref "C46") (pin "1") (pinfunction "1_1") (pintype "passive"))
      (node (ref "C47") (pin "1") (pinfunction "1_1") (pintype "passive"))
      (node (ref "C48") (pin "1") (pinfunction "1_1") (pintype "passive"))
      (node (ref "C49") (pin "1") (pinfunction "1_1") (pintype "passive"))
      (node (ref "C72") (pin "1") (pinfunction "1_1") (pintype "passive"))
      (node (ref "C73") (pin "1") (pinfunction "1_1") (pintype "passive"))
      (node (ref "C74") (pin "1") (pinfunction "1_1") (pintype "passive"))
      (node (ref "C81") (pin "1") (pinfunction "1_1") (pintype "passive"))
      (node (ref "C82") (pin "1") (pinfunction "1_1") (pintype "passive"))
      (node (ref "C83") (pin "1") (pinfunction "1_1") (pintype "passive"))
      (node (ref "SENSOR") (pin "A30") (pinfunction "VDD_PIX_A30") (pintype "power_in"))
      (node (ref "SENSOR") (pin "D28") (pinfunction "VDD_PIX_D28") (pintype "power_in"))
      (node (ref "SENSOR") (pin "D30") (pinfunction "VDD_PIX_D30") (pintype "power_in"))
      (node (ref "SENSOR") (pin "G1") (pinfunction "VDD_PIX_G1") (pintype "power_in"))
      (node (ref "SENSOR") (pin "H28") (pinfunction "VDD_PIX_H28") (pintype "power_in"))
      (node (ref "TP6") (pin "TP") (pinfunction "TP_TP") (pintype "input"))
      (node (ref "X-SOUTH") (pin "49") (pinfunction "49_49") (pintype "bidirectional"))
      (node (ref "X-SOUTH") (pin "55") (pinfunction "55_55") (pintype "bidirectional"))
      (node (ref "X-SOUTH") (pin "61") (pinfunction "61_61") (pintype "bidirectional"))
      (node (ref "X-SOUTH") (pin "67") (pinfunction "67_67") (pintype "bidirectional"))
      (node (ref "X-SOUTH") (pin "73") (pinfunction "73_73") (pintype "bidirectional"))
      (node (ref "X-SOUTH") (pin "79") (pinfunction "79_79") (pintype "bidirectional"))
      (node (ref "X-SOUTH") (pin "85") (pinfunction "85_85") (pintype "bidirectional"))
      (node (ref "X-SOUTH") (pin "91") (pinfunction "91_91") (pintype "bidirectional"))
      (node (ref "X-SOUTH") (pin "97") (pinfunction "97_97") (pintype "bidirectional"))
    )
    (net (code "247") (name "S_VS_CV") (class "Default")
      (node (ref "C12") (pin "1") (pinfunction "1_1") (pintype "passive"))
      (node (ref "R13") (pin "1") (pinfunction "1_1") (pintype "passive"))
      (node (ref "X-SOUTH") (pin "4") (pinfunction "4_4") (pintype "bidirectional"))
    )
    (net (code "248") (name "S_VS_OV") (class "Default")
      (node (ref "USS") (pin "7") (pinfunction "OUTB_7") (pintype "output"))
      (node (ref "X-SOUTH") (pin "3") (pinfunction "3_3") (pintype "bidirectional"))
    )
    (net (code "249") (name "S_VS_UV") (class "Default")
      (node (ref "USS") (pin "1") (pinfunction "OUTA_1") (pintype "output"))
      (node (ref "X-SOUTH") (pin "9") (pinfunction "9_9") (pintype "bidirectional"))
    )
    (net (code "250") (name "S_VW") (class "Default")
      (node (ref "C90") (pin "1") (pinfunction "1_1") (pintype "passive"))
      (node (ref "U3") (pin "1") (pinfunction "BIAS_1") (pintype "power_in"))
      (node (ref "U3") (pin "3") (pinfunction "IN_3") (pintype "power_in"))
      (node (ref "X-SOUTH") (pin "109") (pinfunction "109_109") (pintype "bidirectional"))
      (node (ref "X-SOUTH") (pin "115") (pinfunction "115_115") (pintype "bidirectional"))
      (node (ref "X-SOUTH") (pin "121") (pinfunction "121_121") (pintype "bidirectional"))
      (node (ref "X-SOUTH") (pin "127") (pinfunction "127_127") (pintype "bidirectional"))
      (node (ref "X-SOUTH") (pin "133") (pinfunction "133_133") (pintype "bidirectional"))
    )
    (net (code "251") (name "S_VW_CV") (class "Default")
      (node (ref "C13") (pin "1") (pinfunction "1_1") (pintype "passive"))
      (node (ref "R16") (pin "1") (pinfunction "1_1") (pintype "passive"))
      (node (ref "X-SOUTH") (pin "6") (pinfunction "6_6") (pintype "bidirectional"))
    )
    (net (code "252") (name "S_VW_OV") (class "Default")
      (node (ref "USW") (pin "7") (pinfunction "OUTB_7") (pintype "output"))
      (node (ref "X-SOUTH") (pin "5") (pinfunction "5_5") (pintype "bidirectional"))
    )
    (net (code "253") (name "S_VW_UV") (class "Default")
      (node (ref "USW") (pin "1") (pinfunction "OUTA_1") (pintype "output"))
      (node (ref "X-SOUTH") (pin "11") (pinfunction "11_11") (pintype "bidirectional"))
    )
    (net (code "254") (name "TDIG1") (class "Default")
      (node (ref "SENSOR") (pin "G27") (pinfunction "TDIG1_G27") (pintype "output"))
      (node (ref "U5") (pin "9") (pinfunction "B4_9") (pintype "bidirectional"))
    )
    (net (code "255") (name "TDIG2") (class "Default")
      (node (ref "SENSOR") (pin "G26") (pinfunction "TDIG2_G26") (pintype "output"))
      (node (ref "U6") (pin "11") (pinfunction "B2_11") (pintype "bidirectional"))
    )
    (net (code "256") (name "T_EXP1") (class "Default")
      (node (ref "SENSOR") (pin "H30") (pinfunction "T_EXP1_H30") (pintype "input"))
      (node (ref "U5") (pin "12") (pinfunction "B1_12") (pintype "bidirectional"))
    )
    (net (code "257") (name "T_EXP2") (class "Default")
      (node (ref "SENSOR") (pin "E29") (pinfunction "T_EXP2_E29") (pintype "input"))
      (node (ref "U6") (pin "10") (pinfunction "B3_10") (pintype "bidirectional"))
    )
    (net (code "258") (name "VRAMP1") (class "Default")
      (node (ref "C16") (pin "1") (pinfunction "1_1") (pintype "passive"))
      (node (ref "R23") (pin "1") (pinfunction "1_1") (pintype "passive"))
      (node (ref "SENSOR") (pin "G29") (pinfunction "VRAMP1_G29") (pintype "bidirectional"))
    )
    (net (code "259") (name "VRAMP2") (class "Default")
      (node (ref "C17") (pin "1") (pinfunction "1_1") (pintype "passive"))
      (node (ref "R23") (pin "2") (pinfunction "2_2") (pintype "passive"))
      (node (ref "SENSOR") (pin "F29") (pinfunction "VRAMP2_F29") (pintype "bidirectional"))
    )
    (net (code "260") (name "VTREF") (class "Default")
      (node (ref "C65") (pin "1") (pinfunction "1_1") (pintype "passive"))
      (node (ref "C91") (pin "2") (pinfunction "2_2") (pintype "passive"))
      (node (ref "R21") (pin "2") (pinfunction "2_2") (pintype "passive"))
      (node (ref "R24") (pin "1") (pinfunction "1_1") (pintype "passive"))
      (node (ref "SENSOR") (pin "B2") (pinfunction "VTREF_B2") (pintype "bidirectional"))
      (node (ref "U3") (pin "4") (pinfunction "OUT_4") (pintype "power_in"))
    )
    (net (code "261") (name "VTSIG") (class "Default")
      (node (ref "C66") (pin "1") (pinfunction "1_1") (pintype "passive"))
      (node (ref "R24") (pin "2") (pinfunction "2_2") (pintype "passive"))
      (node (ref "SENSOR") (pin "C2") (pinfunction "VTSIG_C2") (pintype "bidirectional"))
    )
    (net (code "262") (name "unconnected-(U1-NC-Pad2)") (class "Default")
      (node (ref "U1") (pin "2") (pinfunction "NC_2") (pintype "no_connect"))
    )
    (net (code "263") (name "unconnected-(U1-NC-Pad4)") (class "Default")
      (node (ref "U1") (pin "4") (pinfunction "NC_4") (pintype "no_connect"))
    )
    (net (code "264") (name "unconnected-(U1-NC-Pad5)") (class "Default")
      (node (ref "U1") (pin "5") (pinfunction "NC_5") (pintype "no_connect"))
    )
    (net (code "265") (name "unconnected-(U2-NC-Pad2)") (class "Default")
      (node (ref "U2") (pin "2") (pinfunction "NC_2") (pintype "no_connect"))
    )
    (net (code "266") (name "unconnected-(U2-NC-Pad4)") (class "Default")
      (node (ref "U2") (pin "4") (pinfunction "NC_4") (pintype "no_connect"))
    )
    (net (code "267") (name "unconnected-(U2-NC-Pad5)") (class "Default")
      (node (ref "U2") (pin "5") (pinfunction "NC_5") (pintype "no_connect"))
    )
    (net (code "268") (name "unconnected-(U7-OS-Pad3)") (class "Default")
      (node (ref "U7") (pin "3") (pinfunction "OS_3") (pintype "output"))
    )
    (net (code "269") (name "unconnected-(X-NORTH-PadM1)") (class "Default")
      (node (ref "X-NORTH") (pin "M1") (pinfunction "M1_M1") (pintype "bidirectional"))
    )
    (net (code "270") (name "unconnected-(X-NORTH-PadM2)") (class "Default")
      (node (ref "X-NORTH") (pin "M2") (pinfunction "M2_M2") (pintype "bidirectional"))
    )
    (net (code "271") (name "unconnected-(X-SOUTH-PadM1)") (class "Default")
      (node (ref "X-SOUTH") (pin "M1") (pinfunction "M1_M1") (pintype "bidirectional"))
    )
    (net (code "272") (name "unconnected-(X-SOUTH-PadM2)") (class "Default")
      (node (ref "X-SOUTH") (pin "M2") (pinfunction "M2_M2") (pintype "bidirectional"))
    )
  )
)
